# Espressylu-0_7.net
KiCad netlist of a schematic drawn in EAGLE
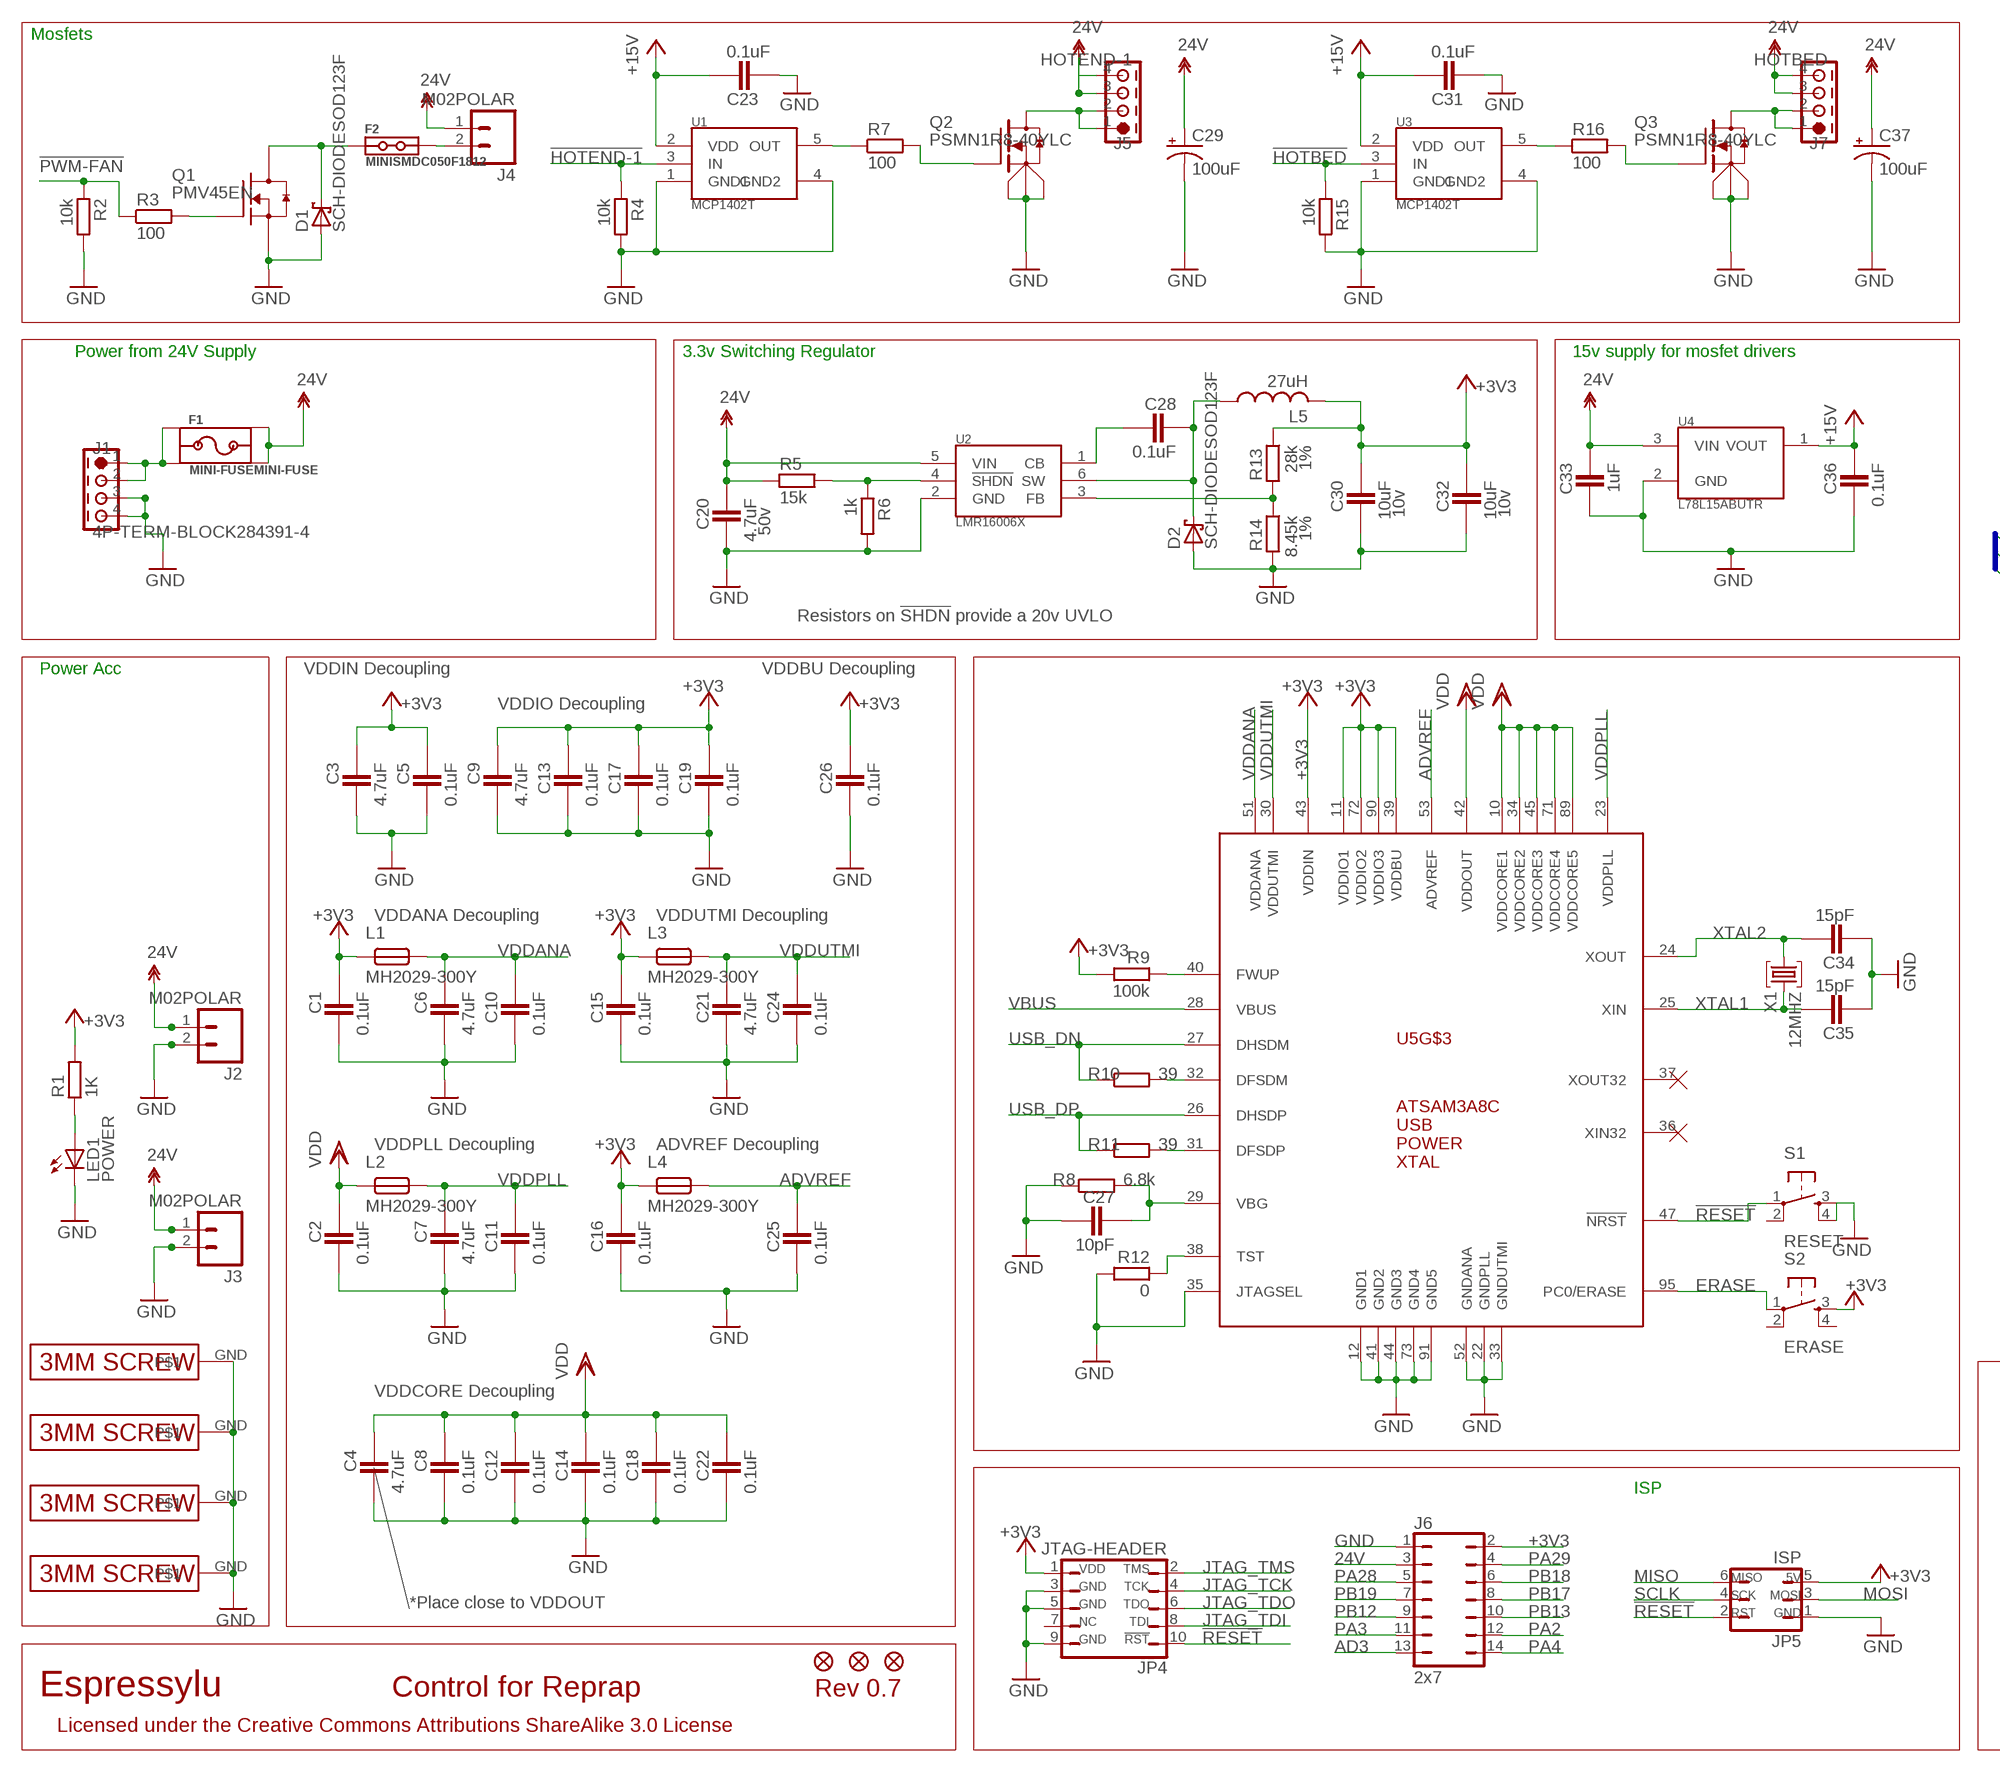
[diagram p0: schematic, sheet 1, part 1 of 2]
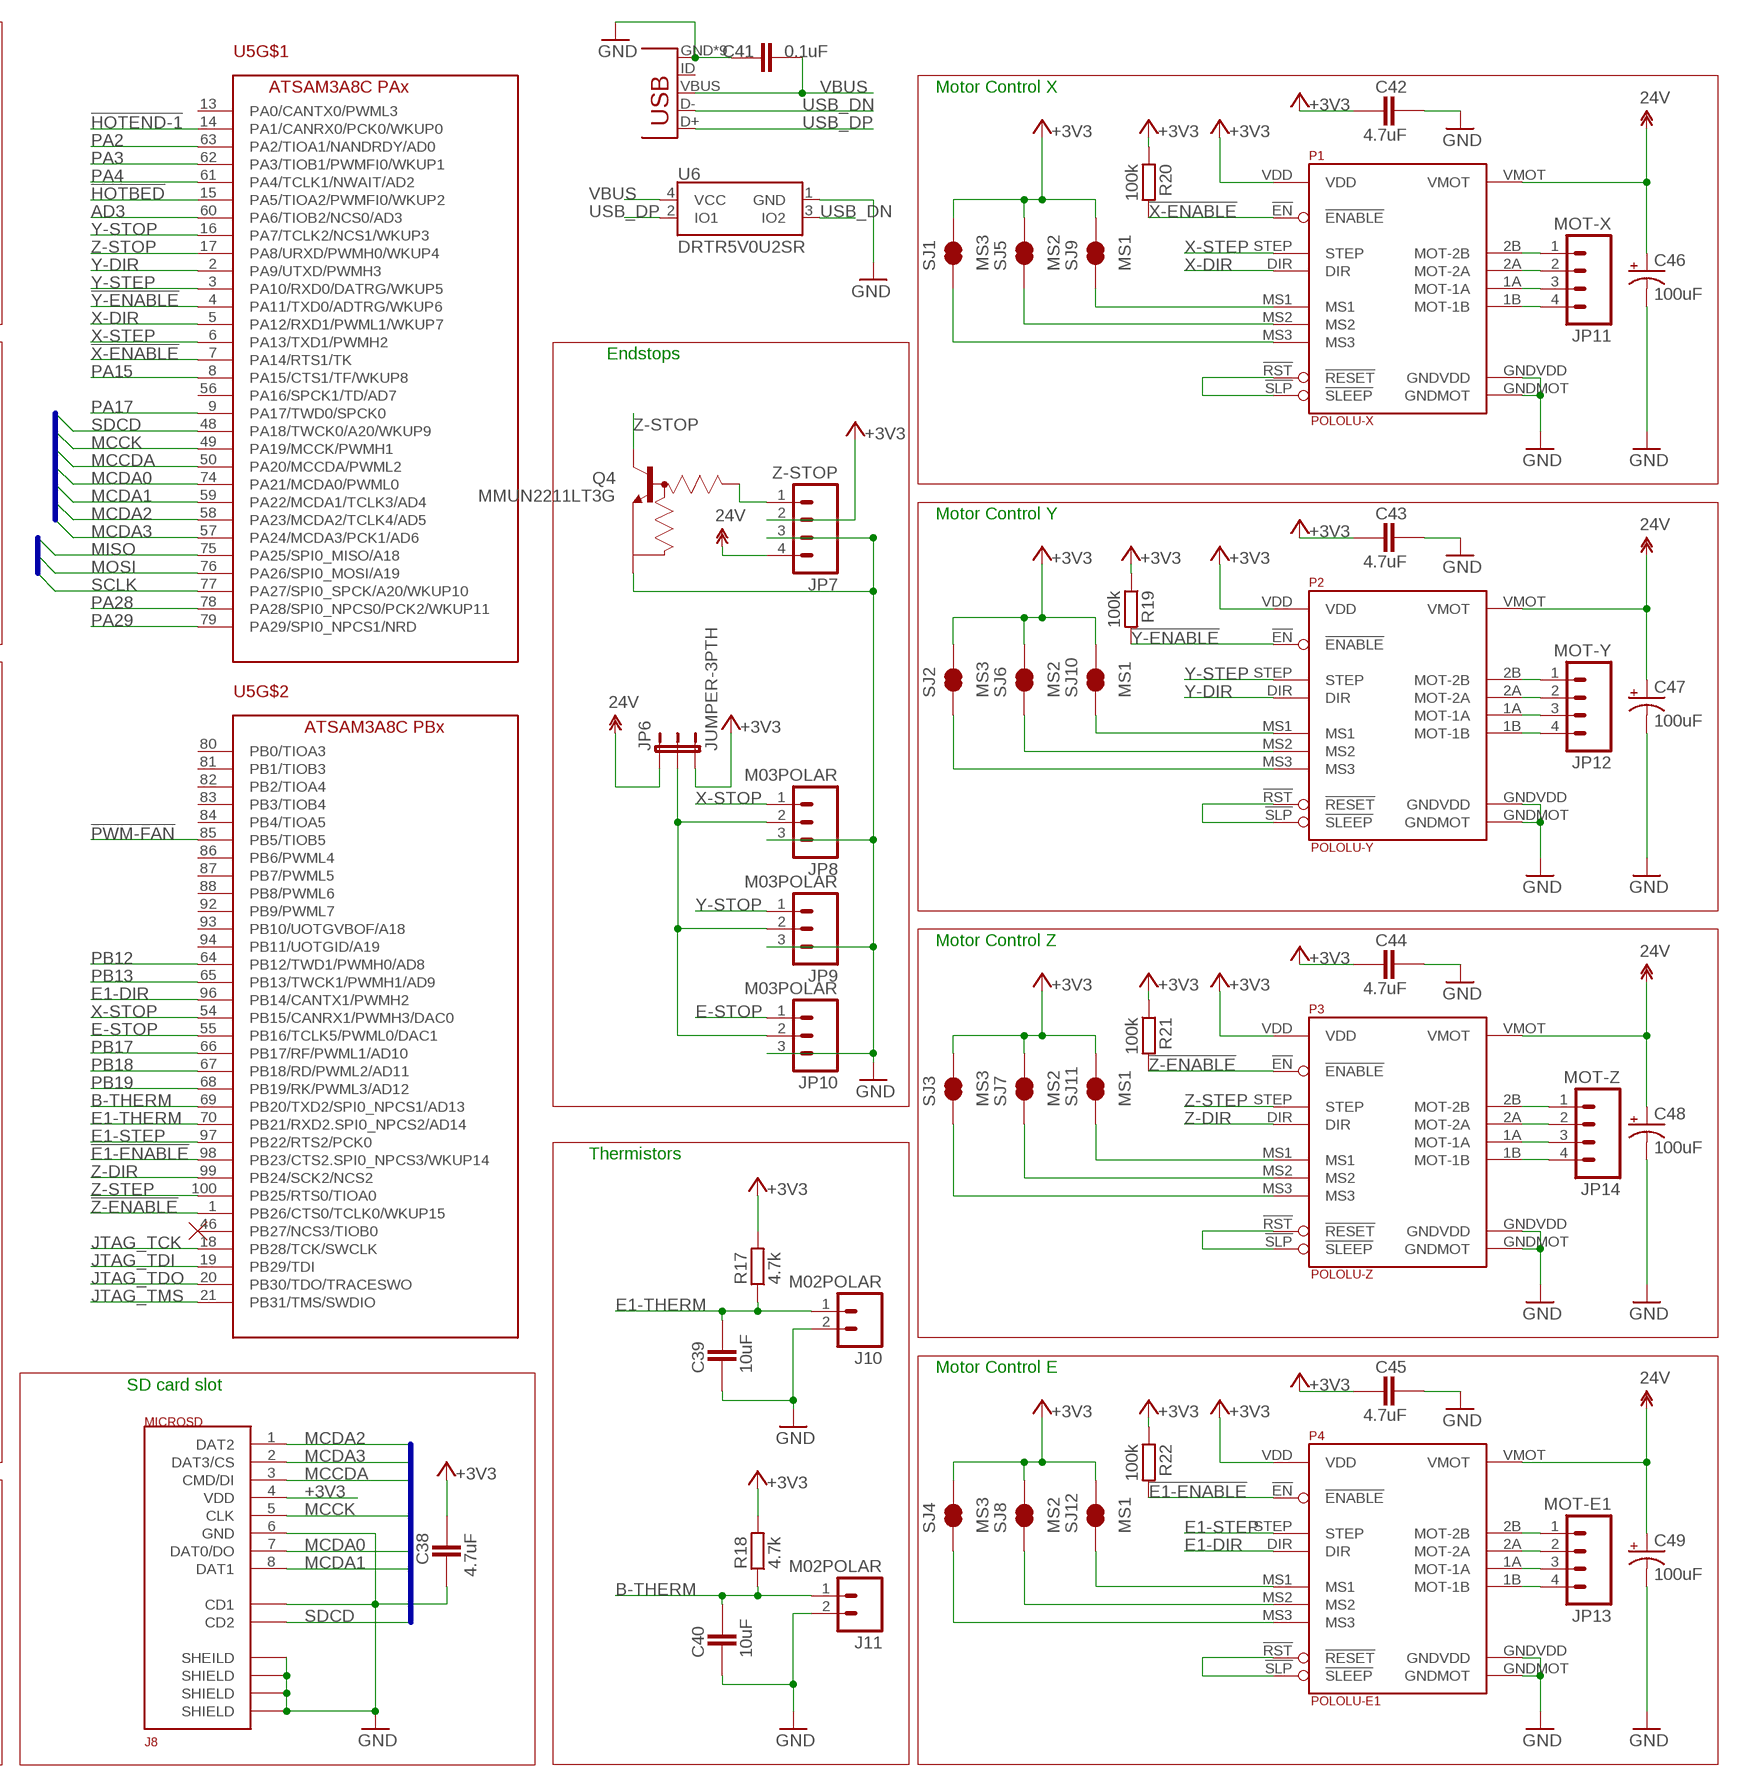
[diagram p1: schematic, sheet 1, part 2 of 2]

(export (version "E")
  (design (tool "Eeschema 10.0.6"))
  (components
    (comp (ref "C1")
      (value "0.1uF")
      (footprint "eagle-import:CAPC1005X60N")
      (fields
        (field (name "MANUFACTURER") "Samsung")
        (field (name "MANUFACTURER_PART_NUMBER") "CL05A104KQ5NNNC")
        (field (name "TOLERANCE") "10%")
      )
      (libsource (lib "eagle-import") (part "CAPACITOR_0402"))
    )
    (comp (ref "C2")
      (value "0.1uF")
      (footprint "eagle-import:CAPC1005X60N")
      (fields
        (field (name "MANUFACTURER") "Samsung")
        (field (name "MANUFACTURER_PART_NUMBER") "CL05A104KQ5NNNC")
        (field (name "TOLERANCE") "10%")
      )
      (libsource (lib "eagle-import") (part "CAPACITOR_0402"))
    )
    (comp (ref "C3")
      (value "4.7uF")
      (footprint "eagle-import:CAPC1608X92N")
      (fields
        (field (name "MANUFACTURER") "Samsung")
        (field (name "MANUFACTURER_PART_NUMBER") "CL10B475KQ8NQNC")
        (field (name "TOLERANCE") "10%")
        (field (name "VDC") "6.3V")
      )
      (libsource (lib "eagle-import") (part "CAPACITOR_0603"))
    )
    (comp (ref "C4")
      (value "4.7uF")
      (footprint "eagle-import:CAPC1608X92N")
      (fields
        (field (name "MANUFACTURER") "Samsung")
        (field (name "MANUFACTURER_PART_NUMBER") "CL10B475KQ8NQNC")
        (field (name "TOLERANCE") "10%")
        (field (name "VDC") "6.3V")
      )
      (libsource (lib "eagle-import") (part "CAPACITOR_0603"))
    )
    (comp (ref "C5")
      (value "0.1uF")
      (footprint "eagle-import:CAPC1005X60N")
      (fields
        (field (name "MANUFACTURER") "Samsung")
        (field (name "MANUFACTURER_PART_NUMBER") "CL05A104KQ5NNNC")
        (field (name "TOLERANCE") "10%")
      )
      (libsource (lib "eagle-import") (part "CAPACITOR_0402"))
    )
    (comp (ref "C6")
      (value "4.7uF")
      (footprint "eagle-import:CAPC1608X92N")
      (fields
        (field (name "MANUFACTURER") "Samsung")
        (field (name "MANUFACTURER_PART_NUMBER") "CL10B475KQ8NQNC")
        (field (name "TOLERANCE") "10%")
        (field (name "VDC") "6.3V")
      )
      (libsource (lib "eagle-import") (part "CAPACITOR_0603"))
    )
    (comp (ref "C7")
      (value "4.7uF")
      (footprint "eagle-import:CAPC1608X92N")
      (fields
        (field (name "MANUFACTURER") "Samsung")
        (field (name "MANUFACTURER_PART_NUMBER") "CL10B475KQ8NQNC")
        (field (name "TOLERANCE") "10%")
        (field (name "VDC") "6.3V")
      )
      (libsource (lib "eagle-import") (part "CAPACITOR_0603"))
    )
    (comp (ref "C8")
      (value "0.1uF")
      (footprint "eagle-import:CAPC1005X60N")
      (fields
        (field (name "MANUFACTURER") "Samsung")
        (field (name "MANUFACTURER_PART_NUMBER") "CL05A104KQ5NNNC")
        (field (name "TOLERANCE") "10%")
      )
      (libsource (lib "eagle-import") (part "CAPACITOR_0402"))
    )
    (comp (ref "C9")
      (value "4.7uF")
      (footprint "eagle-import:CAPC1608X92N")
      (fields
        (field (name "MANUFACTURER") "Samsung")
        (field (name "MANUFACTURER_PART_NUMBER") "CL10B475KQ8NQNC")
        (field (name "TOLERANCE") "10%")
        (field (name "VDC") "6.3V")
      )
      (libsource (lib "eagle-import") (part "CAPACITOR_0603"))
    )
    (comp (ref "C10")
      (value "0.1uF")
      (footprint "eagle-import:CAPC1005X60N")
      (fields
        (field (name "MANUFACTURER") "Samsung")
        (field (name "MANUFACTURER_PART_NUMBER") "CL05A104KQ5NNNC")
        (field (name "TOLERANCE") "10%")
      )
      (libsource (lib "eagle-import") (part "CAPACITOR_0402"))
    )
    (comp (ref "C11")
      (value "0.1uF")
      (footprint "eagle-import:CAPC1005X60N")
      (fields
        (field (name "MANUFACTURER") "Samsung")
        (field (name "MANUFACTURER_PART_NUMBER") "CL05A104KQ5NNNC")
        (field (name "TOLERANCE") "10%")
      )
      (libsource (lib "eagle-import") (part "CAPACITOR_0402"))
    )
    (comp (ref "C12")
      (value "0.1uF")
      (footprint "eagle-import:CAPC1005X60N")
      (fields
        (field (name "MANUFACTURER") "Samsung")
        (field (name "MANUFACTURER_PART_NUMBER") "CL05A104KQ5NNNC")
        (field (name "TOLERANCE") "10%")
      )
      (libsource (lib "eagle-import") (part "CAPACITOR_0402"))
    )
    (comp (ref "C13")
      (value "0.1uF")
      (footprint "eagle-import:CAPC1005X60N")
      (fields
        (field (name "MANUFACTURER") "Samsung")
        (field (name "MANUFACTURER_PART_NUMBER") "CL05A104KQ5NNNC")
        (field (name "TOLERANCE") "10%")
      )
      (libsource (lib "eagle-import") (part "CAPACITOR_0402"))
    )
    (comp (ref "C14")
      (value "0.1uF")
      (footprint "eagle-import:CAPC1005X60N")
      (fields
        (field (name "MANUFACTURER") "Samsung")
        (field (name "MANUFACTURER_PART_NUMBER") "CL05A104KQ5NNNC")
        (field (name "TOLERANCE") "10%")
      )
      (libsource (lib "eagle-import") (part "CAPACITOR_0402"))
    )
    (comp (ref "C15")
      (value "0.1uF")
      (footprint "eagle-import:CAPC1005X60N")
      (fields
        (field (name "MANUFACTURER") "Samsung")
        (field (name "MANUFACTURER_PART_NUMBER") "CL05A104KQ5NNNC")
        (field (name "TOLERANCE") "10%")
      )
      (libsource (lib "eagle-import") (part "CAPACITOR_0402"))
    )
    (comp (ref "C16")
      (value "0.1uF")
      (footprint "eagle-import:CAPC1005X60N")
      (fields
        (field (name "MANUFACTURER") "Samsung")
        (field (name "MANUFACTURER_PART_NUMBER") "CL05A104KQ5NNNC")
        (field (name "TOLERANCE") "10%")
      )
      (libsource (lib "eagle-import") (part "CAPACITOR_0402"))
    )
    (comp (ref "C17")
      (value "0.1uF")
      (footprint "eagle-import:CAPC1005X60N")
      (fields
        (field (name "MANUFACTURER") "Samsung")
        (field (name "MANUFACTURER_PART_NUMBER") "CL05A104KQ5NNNC")
        (field (name "TOLERANCE") "10%")
      )
      (libsource (lib "eagle-import") (part "CAPACITOR_0402"))
    )
    (comp (ref "C18")
      (value "0.1uF")
      (footprint "eagle-import:CAPC1005X60N")
      (fields
        (field (name "MANUFACTURER") "Samsung")
        (field (name "MANUFACTURER_PART_NUMBER") "CL05A104KQ5NNNC")
        (field (name "TOLERANCE") "10%")
      )
      (libsource (lib "eagle-import") (part "CAPACITOR_0402"))
    )
    (comp (ref "C19")
      (value "0.1uF")
      (footprint "eagle-import:CAPC1005X60N")
      (fields
        (field (name "MANUFACTURER") "Samsung")
        (field (name "MANUFACTURER_PART_NUMBER") "CL05A104KQ5NNNC")
        (field (name "TOLERANCE") "10%")
      )
      (libsource (lib "eagle-import") (part "CAPACITOR_0402"))
    )
    (comp (ref "C20")
      (value "4.7uF")
      (footprint "eagle-import:CAPC3215X168N")
      (fields
        (field (name "MANUFACTURER") "Yaiyo Yuden")
        (field (name "MANUFACTURER_PART_NUMBER") "UMK316AB7475KL-T")
        (field (name "TOLERANCE") "10%")
        (field (name "VDC") "50v")
      )
      (libsource (lib "eagle-import") (part "CAPACITOR_1206"))
    )
    (comp (ref "C21")
      (value "4.7uF")
      (footprint "eagle-import:CAPC1608X92N")
      (fields
        (field (name "MANUFACTURER") "Samsung")
        (field (name "MANUFACTURER_PART_NUMBER") "CL10B475KQ8NQNC")
        (field (name "TOLERANCE") "10%")
        (field (name "VDC") "6.3V")
      )
      (libsource (lib "eagle-import") (part "CAPACITOR_0603"))
    )
    (comp (ref "C22")
      (value "0.1uF")
      (footprint "eagle-import:CAPC1005X60N")
      (fields
        (field (name "MANUFACTURER") "Samsung")
        (field (name "MANUFACTURER_PART_NUMBER") "CL05A104KQ5NNNC")
        (field (name "TOLERANCE") "10%")
      )
      (libsource (lib "eagle-import") (part "CAPACITOR_0402"))
    )
    (comp (ref "C23")
      (value "0.1uF")
      (footprint "eagle-import:CAPC1005X60N")
      (fields (field (name "TOLERANCE") "20%"))
      (libsource (lib "eagle-import") (part "CAPACITOR_0402"))
    )
    (comp (ref "C24")
      (value "0.1uF")
      (footprint "eagle-import:CAPC1005X60N")
      (fields
        (field (name "MANUFACTURER") "Samsung")
        (field (name "MANUFACTURER_PART_NUMBER") "CL05A104KQ5NNNC")
        (field (name "TOLERANCE") "10%")
      )
      (libsource (lib "eagle-import") (part "CAPACITOR_0402"))
    )
    (comp (ref "C25")
      (value "0.1uF")
      (footprint "eagle-import:CAPC1005X60N")
      (fields
        (field (name "MANUFACTURER") "Samsung")
        (field (name "MANUFACTURER_PART_NUMBER") "CL05A104KQ5NNNC")
        (field (name "TOLERANCE") "10%")
      )
      (libsource (lib "eagle-import") (part "CAPACITOR_0402"))
    )
    (comp (ref "C26")
      (value "0.1uF")
      (footprint "eagle-import:CAPC1005X60N")
      (fields
        (field (name "MANUFACTURER") "Samsung")
        (field (name "MANUFACTURER_PART_NUMBER") "CL05A104KQ5NNNC")
        (field (name "TOLERANCE") "10%")
      )
      (libsource (lib "eagle-import") (part "CAPACITOR_0402"))
    )
    (comp (ref "C27")
      (value "10pF")
      (footprint "eagle-import:CAPC1005X60N")
      (fields
        (field (name "MANUFACTURER") "Samsung")
        (field (name "MANUFACTURER_PART_NUMBER") "CL10C100JB8NCNC")
        (field (name "TOLERANCE") "5%")
      )
      (libsource (lib "eagle-import") (part "CAPACITOR_0402"))
    )
    (comp (ref "C28")
      (value "0.1uF")
      (footprint "eagle-import:CAPC1005X60N")
      (fields
        (field (name "MANUFACTURER") "Samsung")
        (field (name "MANUFACTURER_PART_NUMBER") "CL10B104KB8NNNC")
        (field (name "TOLERANCE") "10%")
      )
      (libsource (lib "eagle-import") (part "CAPACITOR_0402"))
    )
    (comp (ref "C29")
      (value "100uF")
      (footprint "eagle-import:PANASONIC_D")
      (fields
        (field (name "MANUFACTURER") "Panasonic")
        (field (name "MANUFACTURER_PART_NUMBER") "EEE-FTH101XAP")
        (field (name "TOLERANCE") "20%")
      )
      (libsource (lib "eagle-import") (part "CPOL-USD"))
    )
    (comp (ref "C30")
      (value "10uF")
      (footprint "eagle-import:CAPC2012X145AN")
      (fields
        (field (name "MANUFACTURER") "Murata")
        (field (name "MANUFACTURER_PART_NUMBER") "GRM21BR71A106KE51L")
        (field (name "TOLERANCE") "10%")
        (field (name "VDC") "10v")
      )
      (libsource (lib "eagle-import") (part "CAPACITOR_0805"))
    )
    (comp (ref "C31")
      (value "0.1uF")
      (footprint "eagle-import:CAPC1005X60N")
      (fields (field (name "TOLERANCE") "20%"))
      (libsource (lib "eagle-import") (part "CAPACITOR_0402"))
    )
    (comp (ref "C32")
      (value "10uF")
      (footprint "eagle-import:CAPC2012X145AN")
      (fields
        (field (name "MANUFACTURER") "Murata")
        (field (name "MANUFACTURER_PART_NUMBER") "GRM21BR71A106KE51L")
        (field (name "TOLERANCE") "10%")
        (field (name "VDC") "10v")
      )
      (libsource (lib "eagle-import") (part "CAPACITOR_0805"))
    )
    (comp (ref "C33")
      (value "1uF")
      (footprint "eagle-import:CAPC1005X60N")
      (fields (field (name "TOLERANCE") "20%"))
      (libsource (lib "eagle-import") (part "CAPACITOR_0402"))
    )
    (comp (ref "C34")
      (value "15pF")
      (footprint "eagle-import:CAPC1005X60N")
      (fields
        (field (name "MANUFACTURER") "Samsung")
        (field (name "MANUFACTURER_PART_NUMBER") "CL05C150JB5NNNC")
        (field (name "TOLERANCE") "5%")
      )
      (libsource (lib "eagle-import") (part "CAPACITOR_0402"))
    )
    (comp (ref "C35")
      (value "15pF")
      (footprint "eagle-import:CAPC1005X60N")
      (fields
        (field (name "MANUFACTURER") "Samsung")
        (field (name "MANUFACTURER_PART_NUMBER") "CL05C150JB5NNNC")
        (field (name "TOLERANCE") "5%")
      )
      (libsource (lib "eagle-import") (part "CAPACITOR_0402"))
    )
    (comp (ref "C36")
      (value "0.1uF")
      (footprint "eagle-import:CAPC1005X60N")
      (fields (field (name "TOLERANCE") "20%"))
      (libsource (lib "eagle-import") (part "CAPACITOR_0402"))
    )
    (comp (ref "C37")
      (value "100uF")
      (footprint "eagle-import:PANASONIC_D")
      (fields
        (field (name "MANUFACTURER") "Panasonic")
        (field (name "MANUFACTURER_PART_NUMBER") "EEE-FTH101XAP")
        (field (name "TOLERANCE") "20%")
      )
      (libsource (lib "eagle-import") (part "CPOL-USD"))
    )
    (comp (ref "C38")
      (value "4.7uF")
      (footprint "eagle-import:CAPC1608X92N")
      (fields
        (field (name "MANUFACTURER") "Samsung")
        (field (name "MANUFACTURER_PART_NUMBER") "CL10B475KQ8NQNC")
        (field (name "TOLERANCE") "10%")
        (field (name "VDC") "6.3V")
      )
      (libsource (lib "eagle-import") (part "CAPACITOR_0603"))
    )
    (comp (ref "C39")
      (value "10uF")
      (footprint "eagle-import:CAPC1005X60N")
      (fields
        (field (name "MANUFACTURER") "Murata")
        (field (name "MANUFACTURER_PART_NUMBER") "GRM188R61C106MA73D")
        (field (name "TOLERANCE") "20%")
      )
      (libsource (lib "eagle-import") (part "CAPACITOR_0402"))
    )
    (comp (ref "C40")
      (value "10uF")
      (footprint "eagle-import:CAPC1005X60N")
      (fields
        (field (name "MANUFACTURER") "Murata")
        (field (name "MANUFACTURER_PART_NUMBER") "GRM188R61C106MA73D")
        (field (name "TOLERANCE") "20%")
      )
      (libsource (lib "eagle-import") (part "CAPACITOR_0402"))
    )
    (comp (ref "C41")
      (value "0.1uF")
      (footprint "eagle-import:CAPC1005X60N")
      (fields
        (field (name "MANUFACTURER") "Murata")
        (field (name "MANUFACTURER_PART_NUMBER") "GRM188R71C104KA01D")
        (field (name "TOLERANCE") "10%")
      )
      (libsource (lib "eagle-import") (part "CAPACITOR_0402"))
    )
    (comp (ref "C42")
      (value "4.7uF")
      (footprint "eagle-import:CAPC1608X92N")
      (fields
        (field (name "MANUFACTURER") "Samsung")
        (field (name "MANUFACTURER_PART_NUMBER") "CL10B475KQ8NQNC")
        (field (name "TOLERANCE") "10%")
        (field (name "VDC") "6.3V")
      )
      (libsource (lib "eagle-import") (part "CAPACITOR_0603"))
    )
    (comp (ref "C43")
      (value "4.7uF")
      (footprint "eagle-import:CAPC1608X92N")
      (fields
        (field (name "MANUFACTURER") "Samsung")
        (field (name "MANUFACTURER_PART_NUMBER") "CL10B475KQ8NQNC")
        (field (name "TOLERANCE") "10%")
        (field (name "VDC") "6.3V")
      )
      (libsource (lib "eagle-import") (part "CAPACITOR_0603"))
    )
    (comp (ref "C44")
      (value "4.7uF")
      (footprint "eagle-import:CAPC1608X92N")
      (fields
        (field (name "MANUFACTURER") "Samsung")
        (field (name "MANUFACTURER_PART_NUMBER") "CL10B475KQ8NQNC")
        (field (name "TOLERANCE") "10%")
        (field (name "VDC") "6.3V")
      )
      (libsource (lib "eagle-import") (part "CAPACITOR_0603"))
    )
    (comp (ref "C45")
      (value "4.7uF")
      (footprint "eagle-import:CAPC1608X92N")
      (fields
        (field (name "MANUFACTURER") "Samsung")
        (field (name "MANUFACTURER_PART_NUMBER") "CL10B475KQ8NQNC")
        (field (name "TOLERANCE") "10%")
        (field (name "VDC") "6.3V")
      )
      (libsource (lib "eagle-import") (part "CAPACITOR_0603"))
    )
    (comp (ref "C46")
      (value "100uF")
      (footprint "eagle-import:PANASONIC_D")
      (fields
        (field (name "MANUFACTURER") "Panasonic")
        (field (name "MANUFACTURER_PART_NUMBER") "EEE-FTH101XAP")
        (field (name "TOLERANCE") "20%")
      )
      (libsource (lib "eagle-import") (part "CPOL-USD"))
    )
    (comp (ref "C47")
      (value "100uF")
      (footprint "eagle-import:PANASONIC_D")
      (fields
        (field (name "MANUFACTURER") "Panasonic")
        (field (name "MANUFACTURER_PART_NUMBER") "EEE-FTH101XAP")
        (field (name "TOLERANCE") "20%")
      )
      (libsource (lib "eagle-import") (part "CPOL-USD"))
    )
    (comp (ref "C48")
      (value "100uF")
      (footprint "eagle-import:PANASONIC_D")
      (fields
        (field (name "MANUFACTURER") "Panasonic")
        (field (name "MANUFACTURER_PART_NUMBER") "EEE-FTH101XAP")
        (field (name "TOLERANCE") "20%")
      )
      (libsource (lib "eagle-import") (part "CPOL-USD"))
    )
    (comp (ref "C49")
      (value "100uF")
      (footprint "eagle-import:PANASONIC_D")
      (fields
        (field (name "MANUFACTURER") "Panasonic")
        (field (name "MANUFACTURER_PART_NUMBER") "EEE-FTH101XAP")
        (field (name "TOLERANCE") "20%")
      )
      (libsource (lib "eagle-import") (part "CPOL-USD"))
    )
    (comp (ref "D1")
      (value "SCH-DIODESOD123F")
      (footprint "eagle-import:SOD123F")
      (fields
        (field (name "MANUFACTURER") "NXP Semiconductors")
        (field (name "MANUFACTURER_PART_NUMBER") "PMEG4010CEH,115")
        (field (name "CURRENT") "1A")
        (field (name "MANUFACTURER_1") "NXP Semiconductors")
      )
      (libsource (lib "eagle-import") (part "SCH-DIODESOD123F"))
    )
    (comp (ref "D2")
      (value "SCH-DIODESOD123F")
      (footprint "eagle-import:SOD123F")
      (fields
        (field (name "MANUFACTURER") "NXP Semiconductors")
        (field (name "MANUFACTURER_PART_NUMBER") "PMEG4010CEH,115")
        (field (name "CURRENT") "1A")
        (field (name "MANUFACTURER_1") "NXP Semiconductors")
        (field (name "MANUFACTURER_PART_NUMBER_1") "PMEG4010CEH,115")
        (field (name "REVERSE_VOLTAGE") "40V")
      )
      (libsource (lib "eagle-import") (part "SCH-DIODESOD123F"))
    )
    (comp (ref "F1")
      (value "MINI-FUSEMINI-FUSE")
      (footprint "eagle-import:MINI_FUSE")
      (fields (field (name "MANUFACTURER") "Keystone") (field (name "MANUFACTURER_PART_NUMBER") "3568"))
      (libsource (lib "eagle-import") (part "MINI-FUSEMINI-FUSE"))
    )
    (comp (ref "F2")
      (value "MINISMDC050F1812")
      (footprint "eagle-import:MINISMDC")
      (fields
        (field (name "MANUFACTURER") "TE Connectivity")
        (field (name "MANUFACTURER_PART_NUMBER") "MINISMDC050F-2")
      )
      (libsource (lib "eagle-import") (part "MINISMDC050F1812"))
    )
    (comp (ref "J1")
      (value "4P-TERM-BLOCK284391-4")
      (footprint "eagle-import:284391-4")
      (fields
        (field (name "MANUFACTURER") "TE Connectivity")
        (field (name "MANUFACTURER_PART_NUMBER") "284391-4")
      )
      (libsource (lib "eagle-import") (part "4P-TERM-BLOCK284391-4"))
    )
    (comp (ref "J2")
      (value "M02POLAR")
      (footprint "eagle-import:MOLEX-1X2")
      (description "CONN HEADER 2POS .100 VERT TIN")
      (fields (field (name "MANUFACTURER") "Molex") (field (name "MANUFACTURER_PART_NUMBER") "0022272021"))
      (libsource (lib "eagle-import") (part "M02POLAR"))
    )
    (comp (ref "J3")
      (value "M02POLAR")
      (footprint "eagle-import:MOLEX-1X2")
      (description "CONN HEADER 2POS .100 VERT TIN")
      (fields (field (name "MANUFACTURER") "Molex") (field (name "MANUFACTURER_PART_NUMBER") "0022272021"))
      (libsource (lib "eagle-import") (part "M02POLAR"))
    )
    (comp (ref "J4")
      (value "M02POLAR")
      (footprint "eagle-import:MOLEX-1X2")
      (description "CONN HEADER 2POS .100 VERT TIN")
      (fields (field (name "MANUFACTURER") "Molex") (field (name "MANUFACTURER_PART_NUMBER") "0022272021"))
      (libsource (lib "eagle-import") (part "M02POLAR"))
    )
    (comp (ref "J5")
      (value "HOTEND-1")
      (footprint "eagle-import:284391-4")
      (fields
        (field (name "MANUFACTURER") "TE Connectivity")
        (field (name "MANUFACTURER_PART_NUMBER") "284391-4")
      )
      (libsource (lib "eagle-import") (part "4P-TERM-BLOCK284391-4"))
    )
    (comp (ref "J6")
      (value "2x7")
      (footprint "eagle-import:JP7Q")
      (description "DIL VERTICAL PC TAIL PIN HEADER")
      (fields (field (name "MANUFACTURER") "Harwin") (field (name "MANUFACTURER_PART_NUMBER") "M20-9980746"))
      (libsource (lib "eagle-import") (part "JP7Q"))
    )
    (comp (ref "J7")
      (value "HOTBED")
      (footprint "eagle-import:284391-4")
      (fields
        (field (name "MANUFACTURER") "TE Connectivity")
        (field (name "MANUFACTURER_PART_NUMBER") "284391-4")
      )
      (libsource (lib "eagle-import") (part "4P-TERM-BLOCK284391-4"))
    )
    (comp (ref "J8")
      (value "MICROSD")
      (footprint "eagle-import:AMPHENOL-MICROSD")
      (description "CONN MICRO SD CARD PUSH-PULL R/A")
      (fields
        (field (name "MANUFACTURER") "Amphenol")
        (field (name "MANUFACTURER_PART_NUMBER") "114-00841-68")
      )
      (libsource (lib "eagle-import") (part "MICROSD"))
    )
    (comp (ref "J9")
      (value "USB-MICRO-PTH")
      (footprint "eagle-import:USB-MICROB-PTH")
      (fields (field (name "MANUFACTURER") "FCI") (field (name "MANUFACTURER_PART_NUMBER") "10118194-0001LF"))
      (libsource (lib "eagle-import") (part "USB-MICRO-PTH"))
    )
    (comp (ref "J10")
      (value "M02POLAR")
      (footprint "eagle-import:MOLEX-1X2")
      (description "CONN HEADER 2POS .100 VERT TIN")
      (fields (field (name "MANUFACTURER") "Molex") (field (name "MANUFACTURER_PART_NUMBER") "0022272021"))
      (libsource (lib "eagle-import") (part "M02POLAR"))
    )
    (comp (ref "J11")
      (value "M02POLAR")
      (footprint "eagle-import:MOLEX-1X2")
      (description "CONN HEADER 2POS .100 VERT TIN")
      (fields (field (name "MANUFACTURER") "Molex") (field (name "MANUFACTURER_PART_NUMBER") "0022272021"))
      (libsource (lib "eagle-import") (part "M02POLAR"))
    )
    (comp (ref "JP1")
      (value "FIDUCIAL1X2.5")
      (footprint "eagle-import:FIDUCIAL-1X2.5")
      (libsource (lib "eagle-import") (part "FIDUCIAL1X2.5"))
    )
    (comp (ref "JP2")
      (value "FIDUCIAL1X2.5")
      (footprint "eagle-import:FIDUCIAL-1X2.5")
      (libsource (lib "eagle-import") (part "FIDUCIAL1X2.5"))
    )
    (comp (ref "JP3")
      (value "FIDUCIAL1X2.5")
      (footprint "eagle-import:FIDUCIAL-1X2.5")
      (libsource (lib "eagle-import") (part "FIDUCIAL1X2.5"))
    )
    (comp (ref "JP4")
      (value "JTAG-HEADER")
      (footprint "eagle-import:2X05-0.5-SMD")
      (fields
        (field (name "MANUFACTURER") "FCI")
        (field (name "MANUFACTURER_PART_NUMBER") "20021121-00010C4LF")
      )
      (libsource (lib "eagle-import") (part "JTAG-HEADER"))
    )
    (comp (ref "JP5")
      (value "ISP")
      (footprint "eagle-import:ISP")
      (libsource (lib "eagle-import") (part "PROGHEADER"))
    )
    (comp (ref "JP6")
      (value "JUMPER-3PTH")
      (footprint "eagle-import:1X03")
      (libsource (lib "eagle-import") (part "JUMPER-3PTH"))
    )
    (comp (ref "JP7")
      (value "Z-STOP")
      (footprint "eagle-import:MOLEX-1X4")
      (fields (field (name "MANUFACTURER") "Molex") (field (name "MANUFACTURER_PART_NUMBER") "0022272041"))
      (libsource (lib "eagle-import") (part "M04POLAR"))
    )
    (comp (ref "JP8")
      (value "M03POLAR")
      (footprint "eagle-import:MOLEX-1X3")
      (description "CONN HEADER 3POS .100 VERT TIN")
      (fields (field (name "MANUFACTURER") "Molex") (field (name "MANUFACTURER_PART_NUMBER") "0022272031"))
      (libsource (lib "eagle-import") (part "M03POLAR"))
    )
    (comp (ref "JP9")
      (value "M03POLAR")
      (footprint "eagle-import:MOLEX-1X3")
      (description "CONN HEADER 3POS .100 VERT TIN")
      (fields (field (name "MANUFACTURER") "Molex") (field (name "MANUFACTURER_PART_NUMBER") "0022272031"))
      (libsource (lib "eagle-import") (part "M03POLAR"))
    )
    (comp (ref "JP10")
      (value "M03POLAR")
      (footprint "eagle-import:MOLEX-1X3")
      (description "CONN HEADER 3POS .100 VERT TIN")
      (fields (field (name "MANUFACTURER") "Molex") (field (name "MANUFACTURER_PART_NUMBER") "0022272031"))
      (libsource (lib "eagle-import") (part "M03POLAR"))
    )
    (comp (ref "JP11")
      (value "MOT-X")
      (footprint "eagle-import:MOLEX-1X4")
      (fields (field (name "MANUFACTURER") "Molex") (field (name "MANUFACTURER_PART_NUMBER") "0022272041"))
      (libsource (lib "eagle-import") (part "M04POLAR"))
    )
    (comp (ref "JP12")
      (value "MOT-Y")
      (footprint "eagle-import:MOLEX-1X4")
      (fields (field (name "MANUFACTURER") "Molex") (field (name "MANUFACTURER_PART_NUMBER") "0022272041"))
      (libsource (lib "eagle-import") (part "M04POLAR"))
    )
    (comp (ref "JP13")
      (value "MOT-E1")
      (footprint "eagle-import:MOLEX-1X4")
      (fields (field (name "MANUFACTURER") "Molex") (field (name "MANUFACTURER_PART_NUMBER") "0022272041"))
      (libsource (lib "eagle-import") (part "M04POLAR"))
    )
    (comp (ref "JP14")
      (value "MOT-Z")
      (footprint "eagle-import:MOLEX-1X4")
      (fields (field (name "MANUFACTURER") "Molex") (field (name "MANUFACTURER_PART_NUMBER") "0022272041"))
      (libsource (lib "eagle-import") (part "M04POLAR"))
    )
    (comp (ref "L1")
      (value "MH2029-300Y")
      (footprint "eagle-import:FERRITE_BEAD_0805")
      (description "30 Ohm @ 100MHz")
      (fields (field (name "MANUFACTURER") "Bourns Inc"))
      (libsource (lib "eagle-import") (part "FERRITE_BEAD_0805"))
    )
    (comp (ref "L2")
      (value "MH2029-300Y")
      (footprint "eagle-import:FERRITE_BEAD_0805")
      (description "30 Ohm @ 100MHz")
      (fields (field (name "MANUFACTURER") "Bourns Inc"))
      (libsource (lib "eagle-import") (part "FERRITE_BEAD_0805"))
    )
    (comp (ref "L3")
      (value "MH2029-300Y")
      (footprint "eagle-import:FERRITE_BEAD_0805")
      (description "30 Ohm @ 100MHz")
      (fields (field (name "MANUFACTURER") "Bourns Inc"))
      (libsource (lib "eagle-import") (part "FERRITE_BEAD_0805"))
    )
    (comp (ref "L4")
      (value "MH2029-300Y")
      (footprint "eagle-import:FERRITE_BEAD_0805")
      (description "30 Ohm @ 100MHz")
      (fields (field (name "MANUFACTURER") "Bourns Inc"))
      (libsource (lib "eagle-import") (part "FERRITE_BEAD_0805"))
    )
    (comp (ref "L5")
      (value "27uH")
      (footprint "eagle-import:SDR0604")
      (fields
        (field (name "MANUFACTURER") "Bourns")
        (field (name "MANUFACTURER_1") "Bourns")
        (field (name "MANUFACTURER_PART_NUMBER") "SDR0604-270YL")
      )
      (libsource (lib "eagle-import") (part "INDUCTORSDR0604"))
    )
    (comp (ref "LED1")
      (value "POWER")
      (footprint "eagle-import:CHIPLED_0805")
      (fields
        (field (name "MANUFACTURER") "Kingbright")
        (field (name "MANUFACTURER_PART_NUMBER") "APT2012SGC")
      )
      (libsource (lib "eagle-import") (part "LEDCHIPLED_0805"))
    )
    (comp (ref "P1")
      (value "POLOLU-X")
      (footprint "eagle-import:POLOLU-STEPPER-PTH")
      (libsource (lib "eagle-import") (part "POLOLU-ALLEGRO"))
    )
    (comp (ref "P2")
      (value "POLOLU-Y")
      (footprint "eagle-import:POLOLU-STEPPER-PTH")
      (libsource (lib "eagle-import") (part "POLOLU-ALLEGRO"))
    )
    (comp (ref "P3")
      (value "POLOLU-Z")
      (footprint "eagle-import:POLOLU-STEPPER-PTH")
      (libsource (lib "eagle-import") (part "POLOLU-ALLEGRO"))
    )
    (comp (ref "P4")
      (value "POLOLU-E1")
      (footprint "eagle-import:POLOLU-STEPPER-PTH")
      (libsource (lib "eagle-import") (part "POLOLU-ALLEGRO"))
    )
    (comp (ref "Q1")
      (value "PMV45EN")
      (footprint "eagle-import:SOT23C")
      (fields
        (field (name "MANUFACTURER") "International Rectifier")
        (field (name "MANUFACTURER_PART_NUMBER") "IRLML2060TRPBF")
        (field (name "VOLTAGE") "60V")
      )
      (libsource (lib "eagle-import") (part "MOSFET-NCH_SOT-23"))
    )
    (comp (ref "Q2")
      (value "PSMN1R8-40YLC")
      (footprint "eagle-import:LFPACK-POWERPAK-SO8")
      (fields
        (field (name "MANUFACTURER") "NXP Semiconductors")
        (field (name "MANUFACTURER_PART_NUMBER") "PSMN1R8-40YLC,115")
        (field (name "VOLTAGE") "40V")
      )
      (libsource (lib "eagle-import") (part "PSMN1R8-40YLCPOWERPACK-S08"))
    )
    (comp (ref "Q3")
      (value "PSMN1R8-40YLC")
      (footprint "eagle-import:LFPACK-POWERPAK-SO8")
      (fields
        (field (name "MANUFACTURER") "NXP Semiconductors")
        (field (name "MANUFACTURER_PART_NUMBER") "PSMN1R8-40YLC,115")
        (field (name "VOLTAGE") "40V")
      )
      (libsource (lib "eagle-import") (part "PSMN1R8-40YLCPOWERPACK-S08"))
    )
    (comp (ref "Q4")
      (value "MMUN2211LT3G")
      (footprint "eagle-import:SOT23C")
      (description "TRANS PREBIAS NPN 246MW SOT23-3")
      (fields (field (name "MANUFACTURER") "ON Semiconductor"))
      (libsource (lib "eagle-import") (part "TRANSISTOR_NPN_BIASSOT23C"))
    )
    (comp (ref "R1")
      (value "1K")
      (footprint "eagle-import:RESC1608X55N")
      (libsource (lib "eagle-import") (part "RESISTOR_0603"))
    )
    (comp (ref "R2")
      (value "10k")
      (footprint "eagle-import:RESC1005X40AN")
      (libsource (lib "eagle-import") (part "RESISTOR_0402"))
    )
    (comp (ref "R3")
      (value "100")
      (footprint "eagle-import:RESC1005X40AN")
      (libsource (lib "eagle-import") (part "RESISTOR_0402"))
    )
    (comp (ref "R4")
      (value "10k")
      (footprint "eagle-import:RESC1005X40AN")
      (libsource (lib "eagle-import") (part "RESISTOR_0402"))
    )
    (comp (ref "R5")
      (value "15k")
      (footprint "eagle-import:RESC1005X40AN")
      (libsource (lib "eagle-import") (part "RESISTOR_0402"))
    )
    (comp (ref "R6")
      (value "1k")
      (footprint "eagle-import:RESC1005X40AN")
      (libsource (lib "eagle-import") (part "RESISTOR_0402"))
    )
    (comp (ref "R7")
      (value "100")
      (footprint "eagle-import:RESC1005X40AN")
      (libsource (lib "eagle-import") (part "RESISTOR_0402"))
    )
    (comp (ref "R8")
      (value "6.8k")
      (footprint "eagle-import:RESC1005X40AN")
      (fields (field (name "TOLERANCE") "1%"))
      (libsource (lib "eagle-import") (part "RESISTOR_0402"))
    )
    (comp (ref "R9")
      (value "100k")
      (footprint "eagle-import:RESC1005X40AN")
      (libsource (lib "eagle-import") (part "RESISTOR_0402"))
    )
    (comp (ref "R10")
      (value "39")
      (footprint "eagle-import:RESC1005X40AN")
      (fields (field (name "TOLERANCE") "1%"))
      (libsource (lib "eagle-import") (part "RESISTOR_0402"))
    )
    (comp (ref "R11")
      (value "39")
      (footprint "eagle-import:RESC1005X40AN")
      (fields (field (name "TOLERANCE") "1%"))
      (libsource (lib "eagle-import") (part "RESISTOR_0402"))
    )
    (comp (ref "R12")
      (value "0")
      (footprint "eagle-import:RESC1005X40AN")
      (libsource (lib "eagle-import") (part "RESISTOR_0402"))
    )
    (comp (ref "R13")
      (value "28k")
      (footprint "eagle-import:RESC1005X40AN")
      (fields (field (name "TOLERANCE") "1%"))
      (libsource (lib "eagle-import") (part "RESISTOR_0402"))
    )
    (comp (ref "R14")
      (value "8.45k")
      (footprint "eagle-import:RESC1005X40AN")
      (fields (field (name "TOLERANCE") "1%"))
      (libsource (lib "eagle-import") (part "RESISTOR_0402"))
    )
    (comp (ref "R15")
      (value "10k")
      (footprint "eagle-import:RESC1005X40AN")
      (libsource (lib "eagle-import") (part "RESISTOR_0402"))
    )
    (comp (ref "R16")
      (value "100")
      (footprint "eagle-import:RESC1005X40AN")
      (libsource (lib "eagle-import") (part "RESISTOR_0402"))
    )
    (comp (ref "R17")
      (value "4.7k")
      (footprint "eagle-import:RESC1005X40AN")
      (libsource (lib "eagle-import") (part "RESISTOR_0402"))
    )
    (comp (ref "R18")
      (value "4.7k")
      (footprint "eagle-import:RESC1005X40AN")
      (libsource (lib "eagle-import") (part "RESISTOR_0402"))
    )
    (comp (ref "R19")
      (value "100k")
      (footprint "eagle-import:RESC1005X40AN")
      (libsource (lib "eagle-import") (part "RESISTOR_0402"))
    )
    (comp (ref "R20")
      (value "100k")
      (footprint "eagle-import:RESC1005X40AN")
      (libsource (lib "eagle-import") (part "RESISTOR_0402"))
    )
    (comp (ref "R21")
      (value "100k")
      (footprint "eagle-import:RESC1005X40AN")
      (libsource (lib "eagle-import") (part "RESISTOR_0402"))
    )
    (comp (ref "R22")
      (value "100k")
      (footprint "eagle-import:RESC1005X40AN")
      (libsource (lib "eagle-import") (part "RESISTOR_0402"))
    )
    (comp (ref "S1")
      (value "RESET")
      (footprint "eagle-import:SWITCH-SMD-4P")
      (fields
        (field (name "MANUFACTURER") "TE Connectivity")
        (field (name "MANUFACTURER_PART_NUMBER") "FSM6JSMA")
      )
      (libsource (lib "eagle-import") (part "TAC_SWITCH_4P4P-SMD"))
    )
    (comp (ref "S2")
      (value "ERASE")
      (footprint "eagle-import:SWITCH-SMD-4P")
      (fields
        (field (name "MANUFACTURER") "TE Connectivity")
        (field (name "MANUFACTURER_PART_NUMBER") "FSM6JSMA")
      )
      (libsource (lib "eagle-import") (part "TAC_SWITCH_4P4P-SMD"))
    )
    (comp (ref "SCREW1")
      (value "3MM-SCREW")
      (footprint "eagle-import:PLATEDSCREW")
      (libsource (lib "eagle-import") (part "3MM-SCREW"))
    )
    (comp (ref "SCREW2")
      (value "3MM-SCREW")
      (footprint "eagle-import:PLATEDSCREW")
      (libsource (lib "eagle-import") (part "3MM-SCREW"))
    )
    (comp (ref "SCREW3")
      (value "3MM-SCREW")
      (footprint "eagle-import:PLATEDSCREW")
      (libsource (lib "eagle-import") (part "3MM-SCREW"))
    )
    (comp (ref "SCREW4")
      (value "3MM-SCREW")
      (footprint "eagle-import:PLATEDSCREW")
      (libsource (lib "eagle-import") (part "3MM-SCREW"))
    )
    (comp (ref "SJ1")
      (value "MS3")
      (footprint "eagle-import:SJ_2S-TRACE")
      (libsource (lib "eagle-import") (part "SOLDERJUMPER-NCSJ-TRACE"))
    )
    (comp (ref "SJ2")
      (value "MS3")
      (footprint "eagle-import:SJ_2S-TRACE")
      (libsource (lib "eagle-import") (part "SOLDERJUMPER-NCSJ-TRACE"))
    )
    (comp (ref "SJ3")
      (value "MS3")
      (footprint "eagle-import:SJ_2S-TRACE")
      (libsource (lib "eagle-import") (part "SOLDERJUMPER-NCSJ-TRACE"))
    )
    (comp (ref "SJ4")
      (value "MS3")
      (footprint "eagle-import:SJ_2S-TRACE")
      (libsource (lib "eagle-import") (part "SOLDERJUMPER-NCSJ-TRACE"))
    )
    (comp (ref "SJ5")
      (value "MS2")
      (footprint "eagle-import:SJ_2S-TRACE")
      (libsource (lib "eagle-import") (part "SOLDERJUMPER-NCSJ-TRACE"))
    )
    (comp (ref "SJ6")
      (value "MS2")
      (footprint "eagle-import:SJ_2S-TRACE")
      (libsource (lib "eagle-import") (part "SOLDERJUMPER-NCSJ-TRACE"))
    )
    (comp (ref "SJ7")
      (value "MS2")
      (footprint "eagle-import:SJ_2S-TRACE")
      (libsource (lib "eagle-import") (part "SOLDERJUMPER-NCSJ-TRACE"))
    )
    (comp (ref "SJ8")
      (value "MS2")
      (footprint "eagle-import:SJ_2S-TRACE")
      (libsource (lib "eagle-import") (part "SOLDERJUMPER-NCSJ-TRACE"))
    )
    (comp (ref "SJ9")
      (value "MS1")
      (footprint "eagle-import:SJ_2S-TRACE")
      (libsource (lib "eagle-import") (part "SOLDERJUMPER-NCSJ-TRACE"))
    )
    (comp (ref "SJ10")
      (value "MS1")
      (footprint "eagle-import:SJ_2S-TRACE")
      (libsource (lib "eagle-import") (part "SOLDERJUMPER-NCSJ-TRACE"))
    )
    (comp (ref "SJ11")
      (value "MS1")
      (footprint "eagle-import:SJ_2S-TRACE")
      (libsource (lib "eagle-import") (part "SOLDERJUMPER-NCSJ-TRACE"))
    )
    (comp (ref "SJ12")
      (value "MS1")
      (footprint "eagle-import:SJ_2S-TRACE")
      (libsource (lib "eagle-import") (part "SOLDERJUMPER-NCSJ-TRACE"))
    )
    (comp (ref "U1")
      (value "MCP1402T")
      (footprint "eagle-import:SOT23-5")
      (fields
        (field (name "MANUFACTURER") "Microchip")
        (field (name "MANUFACTURER_PART_NUMBER") "MCP1402T-E/OT")
      )
      (libsource (lib "eagle-import") (part "MCP1402T"))
    )
    (comp (ref "U2")
      (value "LMR16006X")
      (footprint "eagle-import:TSOT6")
      (fields
        (field (name "MANUFACTURER") "Texas Instruments")
        (field (name "MANUFACTURER_PART_NUMBER") "LMR16006XDDCT")
      )
      (libsource (lib "eagle-import") (part "LMR16006X"))
    )
    (comp (ref "U3")
      (value "MCP1402T")
      (footprint "eagle-import:SOT23-5")
      (fields
        (field (name "MANUFACTURER") "Microchip")
        (field (name "MANUFACTURER_PART_NUMBER") "MCP1402T-E/OT")
      )
      (libsource (lib "eagle-import") (part "MCP1402T"))
    )
    (comp (ref "U4")
      (value "L78L15ABUTR")
      (footprint "eagle-import:SOT89")
      (fields (field (name "MANUFACTURER") "STMicroelectronics"))
      (libsource (lib "eagle-import") (part "L78L15ABUTR"))
    )
    (comp (ref "U5")
      (value "ATSAM3A8C-LQFP100")
      (footprint "eagle-import:LQFP100")
      (fields (field (name "MANUFACTURER") "Atmel") (field (name "MANUFACTURER_PART_NUMBER") "ATSAM3A8C"))
      (libsource (lib "eagle-import") (part "ATSAM3A8C-LQFP100"))
    )
    (comp (ref "U6")
      (value "DRTR5V0U2SR")
      (footprint "eagle-import:SOT143-R")
      (fields
        (field (name "MANUFACTURER") "Diodes Incorporated")
        (field (name "MANUFACTURER_PART_NUMBER") "DTR5V0U2SR")
      )
      (libsource (lib "eagle-import") (part "DRTR5V0U2SR"))
    )
    (comp (ref "X1")
      (value "12MHZ")
      (footprint "eagle-import:NDK-XTAL")
      (fields
        (field (name "MANUFACTURER") "Abracon LLC")
        (field (name "MANUFACTURER_PART_NUMBER") "ABM3-12.000MHZ-B2-T")
      )
      (libsource (lib "eagle-import") (part "XTAL"))
    )
  )
  (nets
    (net (code "1") (name "+3V3") (class "Default")
      (node (ref "C1") (pin "1") (pinfunction "1_1") (pintype "passive"))
      (node (ref "C13") (pin "1") (pinfunction "1_1") (pintype "passive"))
      (node (ref "C15") (pin "1") (pinfunction "1_1") (pintype "passive"))
      (node (ref "C16") (pin "1") (pinfunction "1_1") (pintype "passive"))
      (node (ref "C17") (pin "1") (pinfunction "1_1") (pintype "passive"))
      (node (ref "C19") (pin "1") (pinfunction "1_1") (pintype "passive"))
      (node (ref "C26") (pin "1") (pinfunction "1_1") (pintype "passive"))
      (node (ref "C3") (pin "1") (pinfunction "1_1") (pintype "passive"))
      (node (ref "C30") (pin "1") (pinfunction "1_1") (pintype "passive"))
      (node (ref "C32") (pin "1") (pinfunction "1_1") (pintype "passive"))
      (node (ref "C38") (pin "1") (pinfunction "1_1") (pintype "passive"))
      (node (ref "C42") (pin "2") (pinfunction "2_2") (pintype "passive"))
      (node (ref "C43") (pin "2") (pinfunction "2_2") (pintype "passive"))
      (node (ref "C44") (pin "2") (pinfunction "2_2") (pintype "passive"))
      (node (ref "C45") (pin "2") (pinfunction "2_2") (pintype "passive"))
      (node (ref "C5") (pin "1") (pinfunction "1_1") (pintype "passive"))
      (node (ref "C9") (pin "1") (pinfunction "1_1") (pintype "passive"))
      (node (ref "J6") (pin "2") (pinfunction "2_2") (pintype "passive"))
      (node (ref "J8") (pin "4") (pinfunction "VDD_4") (pintype "power_in"))
      (node (ref "JP4") (pin "1") (pinfunction "1_1") (pintype "passive"))
      (node (ref "JP5") (pin "5") (pinfunction "5_5") (pintype "passive"))
      (node (ref "JP6") (pin "3") (pinfunction "3_3") (pintype "passive"))
      (node (ref "JP7") (pin "2") (pinfunction "2_2") (pintype "passive"))
      (node (ref "L1") (pin "1") (pinfunction "1_1") (pintype "passive"))
      (node (ref "L3") (pin "1") (pinfunction "1_1") (pintype "passive"))
      (node (ref "L4") (pin "1") (pinfunction "1_1") (pintype "passive"))
      (node (ref "L5") (pin "2") (pinfunction "2_2") (pintype "passive"))
      (node (ref "P1") (pin "VDD") (pinfunction "VDD_VDD") (pintype "power_in"))
      (node (ref "P2") (pin "VDD") (pinfunction "VDD_VDD") (pintype "power_in"))
      (node (ref "P3") (pin "VDD") (pinfunction "VDD_VDD") (pintype "power_in"))
      (node (ref "P4") (pin "VDD") (pinfunction "VDD_VDD") (pintype "power_in"))
      (node (ref "R1") (pin "2") (pinfunction "2_2") (pintype "passive"))
      (node (ref "R13") (pin "1") (pinfunction "1_1") (pintype "passive"))
      (node (ref "R17") (pin "2") (pinfunction "2_2") (pintype "passive"))
      (node (ref "R18") (pin "2") (pinfunction "2_2") (pintype "passive"))
      (node (ref "R19") (pin "1") (pinfunction "1_1") (pintype "passive"))
      (node (ref "R20") (pin "1") (pinfunction "1_1") (pintype "passive"))
      (node (ref "R21") (pin "1") (pinfunction "1_1") (pintype "passive"))
      (node (ref "R22") (pin "1") (pinfunction "1_1") (pintype "passive"))
      (node (ref "R9") (pin "2") (pinfunction "2_2") (pintype "passive"))
      (node (ref "S2") (pin "3") (pinfunction "3_3") (pintype "passive"))
      (node (ref "SJ1") (pin "2") (pinfunction "2_2") (pintype "passive"))
      (node (ref "SJ10") (pin "2") (pinfunction "2_2") (pintype "passive"))
      (node (ref "SJ11") (pin "2") (pinfunction "2_2") (pintype "passive"))
      (node (ref "SJ12") (pin "2") (pinfunction "2_2") (pintype "passive"))
      (node (ref "SJ2") (pin "2") (pinfunction "2_2") (pintype "passive"))
      (node (ref "SJ3") (pin "2") (pinfunction "2_2") (pintype "passive"))
      (node (ref "SJ4") (pin "2") (pinfunction "2_2") (pintype "passive"))
      (node (ref "SJ5") (pin "2") (pinfunction "2_2") (pintype "passive"))
      (node (ref "SJ6") (pin "2") (pinfunction "2_2") (pintype "passive"))
      (node (ref "SJ7") (pin "2") (pinfunction "2_2") (pintype "passive"))
      (node (ref "SJ8") (pin "2") (pinfunction "2_2") (pintype "passive"))
      (node (ref "SJ9") (pin "2") (pinfunction "2_2") (pintype "passive"))
      (node (ref "U5") (pin "11") (pinfunction "VDDIO1_11") (pintype "power_in"))
      (node (ref "U5") (pin "39") (pinfunction "VDDBU_39") (pintype "power_in"))
      (node (ref "U5") (pin "43") (pinfunction "VDDIN_43") (pintype "power_in"))
      (node (ref "U5") (pin "72") (pinfunction "VDDIO2_72") (pintype "power_in"))
      (node (ref "U5") (pin "90") (pinfunction "VDDIO3_90") (pintype "power_in"))
    )
    (net (code "2") (name "+15V") (class "Default")
      (node (ref "C23") (pin "1") (pinfunction "1_1") (pintype "passive"))
      (node (ref "C31") (pin "1") (pinfunction "1_1") (pintype "passive"))
      (node (ref "C36") (pin "1") (pinfunction "1_1") (pintype "passive"))
      (node (ref "U1") (pin "2") (pinfunction "VDD_2") (pintype "power_in"))
      (node (ref "U3") (pin "2") (pinfunction "VDD_2") (pintype "power_in"))
      (node (ref "U4") (pin "1") (pinfunction "VOUT_1") (pintype "passive"))
    )
    (net (code "3") (name "/AD3") (class "Default")
      (node (ref "J6") (pin "13") (pinfunction "13_13") (pintype "passive"))
      (node (ref "U5") (pin "60") (pinfunction "PA6/TIOB2/NCS0/AD3_60") (pintype "bidirectional"))
    )
    (net (code "4") (name "/ADVREF") (class "Default")
      (node (ref "C25") (pin "1") (pinfunction "1_1") (pintype "passive"))
      (node (ref "L4") (pin "2") (pinfunction "2_2") (pintype "passive"))
      (node (ref "U5") (pin "53") (pinfunction "ADVREF_53") (pintype "power_in"))
    )
    (net (code "5") (name "/B-THERM") (class "Default")
      (node (ref "C40") (pin "2") (pinfunction "2_2") (pintype "passive"))
      (node (ref "J11") (pin "1") (pinfunction "1_1") (pintype "passive"))
      (node (ref "R18") (pin "1") (pinfunction "1_1") (pintype "passive"))
      (node (ref "U5") (pin "69") (pinfunction "PB20/TXD2/SPI0_NPCS1/AD13_69") (pintype "bidirectional"))
    )
    (net (code "6") (name "/E-STOP") (class "Default")
      (node (ref "JP10") (pin "1") (pinfunction "1_1") (pintype "passive"))
      (node (ref "U5") (pin "55") (pinfunction "PB16/TCLK5/PWML0/DAC1_55") (pintype "bidirectional"))
    )
    (net (code "7") (name "/E1-DIR") (class "Default")
      (node (ref "P4") (pin "DIR") (pinfunction "DIR_DIR") (pintype "bidirectional"))
      (node (ref "U5") (pin "96") (pinfunction "PB14/CANTX1/PWMH2_96") (pintype "bidirectional"))
    )
    (net (code "8") (name "/E1-STEP") (class "Default")
      (node (ref "P4") (pin "STEP") (pinfunction "STEP_STEP") (pintype "bidirectional"))
      (node (ref "U5") (pin "97") (pinfunction "PB22/RTS2/PCK0_97") (pintype "bidirectional"))
    )
    (net (code "9") (name "/E1-THERM") (class "Default")
      (node (ref "C39") (pin "2") (pinfunction "2_2") (pintype "passive"))
      (node (ref "J10") (pin "1") (pinfunction "1_1") (pintype "passive"))
      (node (ref "R17") (pin "1") (pinfunction "1_1") (pintype "passive"))
      (node (ref "U5") (pin "70") (pinfunction "PB21/RXD2.SPI0_NPCS2/AD14_70") (pintype "bidirectional"))
    )
    (net (code "10") (name "/ERASE") (class "Default")
      (node (ref "S2") (pin "1") (pinfunction "1_1") (pintype "passive"))
      (node (ref "U5") (pin "95") (pinfunction "PC0/ERASE_95") (pintype "bidirectional"))
    )
    (net (code "11") (name "/JTAG_TCK") (class "Default")
      (node (ref "JP4") (pin "4") (pinfunction "4_4") (pintype "passive"))
      (node (ref "U5") (pin "18") (pinfunction "PB28/TCK/SWCLK_18") (pintype "bidirectional"))
    )
    (net (code "12") (name "/JTAG_TDI") (class "Default")
      (node (ref "JP4") (pin "8") (pinfunction "8_8") (pintype "passive"))
      (node (ref "U5") (pin "19") (pinfunction "PB29/TDI_19") (pintype "bidirectional"))
    )
    (net (code "13") (name "/JTAG_TDO") (class "Default")
      (node (ref "JP4") (pin "6") (pinfunction "6_6") (pintype "passive"))
      (node (ref "U5") (pin "20") (pinfunction "PB30/TDO/TRACESWO_20") (pintype "bidirectional"))
    )
    (net (code "14") (name "/JTAG_TMS") (class "Default")
      (node (ref "JP4") (pin "2") (pinfunction "2_2") (pintype "passive"))
      (node (ref "U5") (pin "21") (pinfunction "PB31/TMS/SWDIO_21") (pintype "bidirectional"))
    )
    (net (code "15") (name "/MCCDA") (class "Default")
      (node (ref "J8") (pin "3") (pinfunction "CMD/DI_3") (pintype "input"))
      (node (ref "U5") (pin "50") (pinfunction "PA20/MCCDA/PWML2_50") (pintype "bidirectional"))
    )
    (net (code "16") (name "/MCCK") (class "Default")
      (node (ref "J8") (pin "5") (pinfunction "CLK_5") (pintype "input"))
      (node (ref "U5") (pin "49") (pinfunction "PA19/MCCK/PWMH1_49") (pintype "bidirectional"))
    )
    (net (code "17") (name "/MCDA0") (class "Default")
      (node (ref "J8") (pin "7") (pinfunction "DAT0/DO_7") (pintype "bidirectional"))
      (node (ref "U5") (pin "74") (pinfunction "PA21/MCDA0/PWML0_74") (pintype "bidirectional"))
    )
    (net (code "18") (name "/MCDA1") (class "Default")
      (node (ref "J8") (pin "8") (pinfunction "DAT1_8") (pintype "bidirectional"))
      (node (ref "U5") (pin "59") (pinfunction "PA22/MCDA1/TCLK3/AD4_59") (pintype "bidirectional"))
    )
    (net (code "19") (name "/MCDA2") (class "Default")
      (node (ref "J8") (pin "1") (pinfunction "DAT2_1") (pintype "bidirectional"))
      (node (ref "U5") (pin "58") (pinfunction "PA23/MCDA2/TCLK4/AD5_58") (pintype "bidirectional"))
    )
    (net (code "20") (name "/MCDA3") (class "Default")
      (node (ref "J8") (pin "2") (pinfunction "DAT3/CS_2") (pintype "bidirectional"))
      (node (ref "U5") (pin "57") (pinfunction "PA24/MCDA3/PCK1/AD6_57") (pintype "bidirectional"))
    )
    (net (code "21") (name "/MISO") (class "Default")
      (node (ref "JP5") (pin "6") (pinfunction "6_6") (pintype "passive"))
      (node (ref "U5") (pin "75") (pinfunction "PA25/SPI0_MISO/A18_75") (pintype "bidirectional"))
    )
    (net (code "22") (name "/MOSI") (class "Default")
      (node (ref "JP5") (pin "3") (pinfunction "3_3") (pintype "passive"))
      (node (ref "U5") (pin "76") (pinfunction "PA26/SPI0_MOSI/A19_76") (pintype "bidirectional"))
    )
    (net (code "23") (name "/PA2") (class "Default")
      (node (ref "J6") (pin "12") (pinfunction "12_12") (pintype "passive"))
      (node (ref "U5") (pin "63") (pinfunction "PA2/TIOA1/NANDRDY/AD0_63") (pintype "bidirectional"))
    )
    (net (code "24") (name "/PA3") (class "Default")
      (node (ref "J6") (pin "11") (pinfunction "11_11") (pintype "passive"))
      (node (ref "U5") (pin "62") (pinfunction "PA3/TIOB1/PWMFI0/WKUP1_62") (pintype "bidirectional"))
    )
    (net (code "25") (name "/PA4") (class "Default")
      (node (ref "J6") (pin "14") (pinfunction "14_14") (pintype "passive"))
      (node (ref "U5") (pin "61") (pinfunction "PA4/TCLK1/NWAIT/AD2_61") (pintype "bidirectional"))
    )
    (net (code "26") (name "/PA15") (class "Default")
      (node (ref "U5") (pin "8") (pinfunction "PA15/CTS1/TF/WKUP8_8") (pintype "bidirectional"))
    )
    (net (code "27") (name "/PA17") (class "Default")
      (node (ref "U5") (pin "9") (pinfunction "PA17/TWD0/SPCK0_9") (pintype "bidirectional"))
    )
    (net (code "28") (name "/PA28") (class "Default")
      (node (ref "J6") (pin "5") (pinfunction "5_5") (pintype "passive"))
      (node (ref "U5") (pin "78") (pinfunction "PA28/SPI0_NPCS0/PCK2/WKUP11_78") (pintype "bidirectional"))
    )
    (net (code "29") (name "/PA29") (class "Default")
      (node (ref "J6") (pin "4") (pinfunction "4_4") (pintype "passive"))
      (node (ref "U5") (pin "79") (pinfunction "PA29/SPI0_NPCS1/NRD_79") (pintype "bidirectional"))
    )
    (net (code "30") (name "/PB12") (class "Default")
      (node (ref "J6") (pin "9") (pinfunction "9_9") (pintype "passive"))
      (node (ref "U5") (pin "64") (pinfunction "PB12/TWD1/PWMH0/AD8_64") (pintype "bidirectional"))
    )
    (net (code "31") (name "/PB13") (class "Default")
      (node (ref "J6") (pin "10") (pinfunction "10_10") (pintype "passive"))
      (node (ref "U5") (pin "65") (pinfunction "PB13/TWCK1/PWMH1/AD9_65") (pintype "bidirectional"))
    )
    (net (code "32") (name "/PB17") (class "Default")
      (node (ref "J6") (pin "8") (pinfunction "8_8") (pintype "passive"))
      (node (ref "U5") (pin "66") (pinfunction "PB17/RF/PWML1/AD10_66") (pintype "bidirectional"))
    )
    (net (code "33") (name "/PB18") (class "Default")
      (node (ref "J6") (pin "6") (pinfunction "6_6") (pintype "passive"))
      (node (ref "U5") (pin "67") (pinfunction "PB18/RD/PWML2/AD11_67") (pintype "bidirectional"))
    )
    (net (code "34") (name "/PB19") (class "Default")
      (node (ref "J6") (pin "7") (pinfunction "7_7") (pintype "passive"))
      (node (ref "U5") (pin "68") (pinfunction "PB19/RK/PWML3/AD12_68") (pintype "bidirectional"))
    )
    (net (code "35") (name "/SCLK") (class "Default")
      (node (ref "JP5") (pin "4") (pinfunction "4_4") (pintype "passive"))
      (node (ref "U5") (pin "77") (pinfunction "PA27/SPI0_SPCK/A20/WKUP10_77") (pintype "bidirectional"))
    )
    (net (code "36") (name "/SDCD") (class "Default")
      (node (ref "J8") (pin "CD2") (pinfunction "CD2_CD2") (pintype "bidirectional"))
      (node (ref "U5") (pin "48") (pinfunction "PA18/TWCK0/A20/WKUP9_48") (pintype "bidirectional"))
    )
    (net (code "37") (name "/USB_DN") (class "Default")
      (node (ref "J9") (pin "D-") (pinfunction "D-_D-") (pintype "bidirectional"))
      (node (ref "R10") (pin "1") (pinfunction "1_1") (pintype "passive"))
      (node (ref "U5") (pin "27") (pinfunction "DHSDM_27") (pintype "bidirectional"))
      (node (ref "U6") (pin "3") (pinfunction "IO2_3") (pintype "bidirectional"))
    )
    (net (code "38") (name "/USB_DP") (class "Default")
      (node (ref "J9") (pin "D+") (pinfunction "D+_D+") (pintype "bidirectional"))
      (node (ref "R11") (pin "1") (pinfunction "1_1") (pintype "passive"))
      (node (ref "U5") (pin "26") (pinfunction "DHSDP_26") (pintype "bidirectional"))
      (node (ref "U6") (pin "2") (pinfunction "IO1_2") (pintype "bidirectional"))
    )
    (net (code "39") (name "/VBUS") (class "Default")
      (node (ref "C41") (pin "2") (pinfunction "2_2") (pintype "passive"))
      (node (ref "J9") (pin "VBUS") (pinfunction "VBUS_VBUS") (pintype "bidirectional"))
      (node (ref "U5") (pin "28") (pinfunction "VBUS_28") (pintype "power_in"))
      (node (ref "U6") (pin "4") (pinfunction "VCC_4") (pintype "power_in"))
    )
    (net (code "40") (name "/VDDANA") (class "Default")
      (node (ref "C10") (pin "1") (pinfunction "1_1") (pintype "passive"))
      (node (ref "C6") (pin "1") (pinfunction "1_1") (pintype "passive"))
      (node (ref "L1") (pin "2") (pinfunction "2_2") (pintype "passive"))
      (node (ref "U5") (pin "51") (pinfunction "VDDANA_51") (pintype "power_in"))
    )
    (net (code "41") (name "/VDDPLL") (class "Default")
      (node (ref "C11") (pin "1") (pinfunction "1_1") (pintype "passive"))
      (node (ref "C7") (pin "1") (pinfunction "1_1") (pintype "passive"))
      (node (ref "L2") (pin "2") (pinfunction "2_2") (pintype "passive"))
      (node (ref "U5") (pin "23") (pinfunction "VDDPLL_23") (pintype "input"))
    )
    (net (code "42") (name "/VDDUTMI") (class "Default")
      (node (ref "C21") (pin "1") (pinfunction "1_1") (pintype "passive"))
      (node (ref "C24") (pin "1") (pinfunction "1_1") (pintype "passive"))
      (node (ref "L3") (pin "2") (pinfunction "2_2") (pintype "passive"))
      (node (ref "U5") (pin "30") (pinfunction "VDDUTMI_30") (pintype "input"))
    )
    (net (code "43") (name "/X-DIR") (class "Default")
      (node (ref "P1") (pin "DIR") (pinfunction "DIR_DIR") (pintype "bidirectional"))
      (node (ref "U5") (pin "5") (pinfunction "PA12/RXD1/PWML1/WKUP7_5") (pintype "bidirectional"))
    )
    (net (code "44") (name "/X-STEP") (class "Default")
      (node (ref "P1") (pin "STEP") (pinfunction "STEP_STEP") (pintype "bidirectional"))
      (node (ref "U5") (pin "6") (pinfunction "PA13/TXD1/PWMH2_6") (pintype "bidirectional"))
    )
    (net (code "45") (name "/X-STOP") (class "Default")
      (node (ref "JP8") (pin "1") (pinfunction "1_1") (pintype "passive"))
      (node (ref "U5") (pin "54") (pinfunction "PB15/CANRX1/PWMH3/DAC0_54") (pintype "bidirectional"))
    )
    (net (code "46") (name "/XTAL1") (class "Default")
      (node (ref "C35") (pin "2") (pinfunction "2_2") (pintype "passive"))
      (node (ref "U5") (pin "25") (pinfunction "XIN_25") (pintype "input"))
      (node (ref "X1") (pin "P$2") (pinfunction "2_P$2") (pintype "passive"))
    )
    (net (code "47") (name "/XTAL2") (class "Default")
      (node (ref "C34") (pin "2") (pinfunction "2_2") (pintype "passive"))
      (node (ref "U5") (pin "24") (pinfunction "XOUT_24") (pintype "output"))
      (node (ref "X1") (pin "P$1") (pinfunction "1_P$1") (pintype "passive"))
    )
    (net (code "48") (name "/Y-DIR") (class "Default")
      (node (ref "P2") (pin "DIR") (pinfunction "DIR_DIR") (pintype "bidirectional"))
      (node (ref "U5") (pin "2") (pinfunction "PA9/UTXD/PWMH3_2") (pintype "bidirectional"))
    )
    (net (code "49") (name "/Y-STEP") (class "Default")
      (node (ref "P2") (pin "STEP") (pinfunction "STEP_STEP") (pintype "bidirectional"))
      (node (ref "U5") (pin "3") (pinfunction "PA10/RXD0/DATRG/WKUP5_3") (pintype "bidirectional"))
    )
    (net (code "50") (name "/Y-STOP") (class "Default")
      (node (ref "JP9") (pin "1") (pinfunction "1_1") (pintype "passive"))
      (node (ref "U5") (pin "16") (pinfunction "PA7/TCLK2/NCS1/WKUP3_16") (pintype "bidirectional"))
    )
    (net (code "51") (name "/Z-DIR") (class "Default")
      (node (ref "P3") (pin "DIR") (pinfunction "DIR_DIR") (pintype "bidirectional"))
      (node (ref "U5") (pin "99") (pinfunction "PB24/SCK2/NCS2_99") (pintype "bidirectional"))
    )
    (net (code "52") (name "/Z-STEP") (class "Default")
      (node (ref "P3") (pin "STEP") (pinfunction "STEP_STEP") (pintype "bidirectional"))
      (node (ref "U5") (pin "100") (pinfunction "PB25/RTS0/TIOA0_100") (pintype "bidirectional"))
    )
    (net (code "53") (name "/Z-STOP") (class "Default")
      (node (ref "Q4") (pin "3") (pinfunction "C_3") (pintype "passive"))
      (node (ref "U5") (pin "17") (pinfunction "PA8/URXD/PWMH0/WKUP4_17") (pintype "bidirectional"))
    )
    (net (code "54") (name "/~{E1-ENABLE}") (class "Default")
      (node (ref "P4") (pin "!EN") (pinfunction "~{ENABLE}_!EN") (pintype "input"))
      (node (ref "R22") (pin "2") (pinfunction "2_2") (pintype "passive"))
      (node (ref "U5") (pin "98") (pinfunction "PB23/CTS2.SPI0_NPCS3/WKUP14_98") (pintype "bidirectional"))
    )
    (net (code "55") (name "/~{HOTBED}") (class "Default")
      (node (ref "R15") (pin "1") (pinfunction "1_1") (pintype "passive"))
      (node (ref "U3") (pin "3") (pinfunction "IN_3") (pintype "input"))
      (node (ref "U5") (pin "15") (pinfunction "PA5/TIOA2/PWMFI0/WKUP2_15") (pintype "bidirectional"))
    )
    (net (code "56") (name "/~{HOTEND-1}") (class "Default")
      (node (ref "R4") (pin "1") (pinfunction "1_1") (pintype "passive"))
      (node (ref "U1") (pin "3") (pinfunction "IN_3") (pintype "input"))
      (node (ref "U5") (pin "14") (pinfunction "PA1/CANRX0/PCK0/WKUP0_14") (pintype "bidirectional"))
    )
    (net (code "57") (name "/~{PWM-FAN}") (class "Default")
      (node (ref "R2") (pin "1") (pinfunction "1_1") (pintype "passive"))
      (node (ref "R3") (pin "1") (pinfunction "1_1") (pintype "passive"))
      (node (ref "U5") (pin "85") (pinfunction "PB5/TIOB5_85") (pintype "bidirectional"))
    )
    (net (code "58") (name "/~{RESET}") (class "Default")
      (node (ref "JP4") (pin "10") (pinfunction "10_10") (pintype "passive"))
      (node (ref "JP5") (pin "2") (pinfunction "2_2") (pintype "passive"))
      (node (ref "S1") (pin "1") (pinfunction "1_1") (pintype "passive"))
      (node (ref "U5") (pin "47") (pinfunction "~{NRST}_47") (pintype "bidirectional"))
    )
    (net (code "59") (name "/~{X-ENABLE}") (class "Default")
      (node (ref "P1") (pin "!EN") (pinfunction "~{ENABLE}_!EN") (pintype "input"))
      (node (ref "R20") (pin "2") (pinfunction "2_2") (pintype "passive"))
      (node (ref "U5") (pin "7") (pinfunction "PA14/RTS1/TK_7") (pintype "bidirectional"))
    )
    (net (code "60") (name "/~{Y-ENABLE}") (class "Default")
      (node (ref "P2") (pin "!EN") (pinfunction "~{ENABLE}_!EN") (pintype "input"))
      (node (ref "R19") (pin "2") (pinfunction "2_2") (pintype "passive"))
      (node (ref "U5") (pin "4") (pinfunction "PA11/TXD0/ADTRG/WKUP6_4") (pintype "bidirectional"))
    )
    (net (code "61") (name "/~{Z-ENABLE}") (class "Default")
      (node (ref "P3") (pin "!EN") (pinfunction "~{ENABLE}_!EN") (pintype "input"))
      (node (ref "R21") (pin "2") (pinfunction "2_2") (pintype "passive"))
      (node (ref "U5") (pin "1") (pinfunction "PB26/CTS0/TCLK0/WKUP15_1") (pintype "bidirectional"))
    )
    (net (code "62") (name "24V") (class "Default")
      (node (ref "C20") (pin "1") (pinfunction "1_1") (pintype "passive"))
      (node (ref "C29") (pin "+") (pinfunction "+_+") (pintype "passive"))
      (node (ref "C33") (pin "1") (pinfunction "1_1") (pintype "passive"))
      (node (ref "C37") (pin "+") (pinfunction "+_+") (pintype "passive"))
      (node (ref "C46") (pin "+") (pinfunction "+_+") (pintype "passive"))
      (node (ref "C47") (pin "+") (pinfunction "+_+") (pintype "passive"))
      (node (ref "C48") (pin "+") (pinfunction "+_+") (pintype "passive"))
      (node (ref "C49") (pin "+") (pinfunction "+_+") (pintype "passive"))
      (node (ref "F1") (pin "P$3") (pinfunction "P$3_P$3") (pintype "passive"))
      (node (ref "F1") (pin "P$4") (pinfunction "P$4_P$4") (pintype "passive"))
      (node (ref "J2") (pin "1") (pinfunction "1_1") (pintype "passive"))
      (node (ref "J3") (pin "1") (pinfunction "1_1") (pintype "passive"))
      (node (ref "J4") (pin "1") (pinfunction "1_1") (pintype "passive"))
      (node (ref "J5") (pin "3") (pinfunction "3_3") (pintype "power_in"))
      (node (ref "J5") (pin "4") (pinfunction "4_4") (pintype "power_in"))
      (node (ref "J6") (pin "3") (pinfunction "3_3") (pintype "passive"))
      (node (ref "J7") (pin "3") (pinfunction "3_3") (pintype "power_in"))
      (node (ref "J7") (pin "4") (pinfunction "4_4") (pintype "power_in"))
      (node (ref "JP6") (pin "1") (pinfunction "1_1") (pintype "passive"))
      (node (ref "JP7") (pin "4") (pinfunction "4_4") (pintype "passive"))
      (node (ref "P1") (pin "VMOT") (pinfunction "VMOT_VMOT") (pintype "power_in"))
      (node (ref "P2") (pin "VMOT") (pinfunction "VMOT_VMOT") (pintype "power_in"))
      (node (ref "P3") (pin "VMOT") (pinfunction "VMOT_VMOT") (pintype "power_in"))
      (node (ref "P4") (pin "VMOT") (pinfunction "VMOT_VMOT") (pintype "power_in"))
      (node (ref "R5") (pin "1") (pinfunction "1_1") (pintype "passive"))
      (node (ref "U2") (pin "5") (pinfunction "VIN_5") (pintype "power_in"))
      (node (ref "U4") (pin "3") (pinfunction "VIN_3") (pintype "power_in"))
    )
    (net (code "63") (name "GND") (class "Default")
      (node (ref "C1") (pin "2") (pinfunction "2_2") (pintype "passive"))
      (node (ref "C10") (pin "2") (pinfunction "2_2") (pintype "passive"))
      (node (ref "C11") (pin "2") (pinfunction "2_2") (pintype "passive"))
      (node (ref "C12") (pin "2") (pinfunction "2_2") (pintype "passive"))
      (node (ref "C13") (pin "2") (pinfunction "2_2") (pintype "passive"))
      (node (ref "C14") (pin "2") (pinfunction "2_2") (pintype "passive"))
      (node (ref "C15") (pin "2") (pinfunction "2_2") (pintype "passive"))
      (node (ref "C16") (pin "2") (pinfunction "2_2") (pintype "passive"))
      (node (ref "C17") (pin "2") (pinfunction "2_2") (pintype "passive"))
      (node (ref "C18") (pin "2") (pinfunction "2_2") (pintype "passive"))
      (node (ref "C19") (pin "2") (pinfunction "2_2") (pintype "passive"))
      (node (ref "C2") (pin "2") (pinfunction "2_2") (pintype "passive"))
      (node (ref "C20") (pin "2") (pinfunction "2_2") (pintype "passive"))
      (node (ref "C21") (pin "2") (pinfunction "2_2") (pintype "passive"))
      (node (ref "C22") (pin "2") (pinfunction "2_2") (pintype "passive"))
      (node (ref "C23") (pin "2") (pinfunction "2_2") (pintype "passive"))
      (node (ref "C24") (pin "2") (pinfunction "2_2") (pintype "passive"))
      (node (ref "C25") (pin "2") (pinfunction "2_2") (pintype "passive"))
      (node (ref "C26") (pin "2") (pinfunction "2_2") (pintype "passive"))
      (node (ref "C27") (pin "2") (pinfunction "2_2") (pintype "passive"))
      (node (ref "C29") (pin "-") (pinfunction "-_-") (pintype "passive"))
      (node (ref "C3") (pin "2") (pinfunction "2_2") (pintype "passive"))
      (node (ref "C30") (pin "2") (pinfunction "2_2") (pintype "passive"))
      (node (ref "C31") (pin "2") (pinfunction "2_2") (pintype "passive"))
      (node (ref "C32") (pin "2") (pinfunction "2_2") (pintype "passive"))
      (node (ref "C33") (pin "2") (pinfunction "2_2") (pintype "passive"))
      (node (ref "C34") (pin "1") (pinfunction "1_1") (pintype "passive"))
      (node (ref "C35") (pin "1") (pinfunction "1_1") (pintype "passive"))
      (node (ref "C36") (pin "2") (pinfunction "2_2") (pintype "passive"))
      (node (ref "C37") (pin "-") (pinfunction "-_-") (pintype "passive"))
      (node (ref "C38") (pin "2") (pinfunction "2_2") (pintype "passive"))
      (node (ref "C39") (pin "1") (pinfunction "1_1") (pintype "passive"))
      (node (ref "C4") (pin "2") (pinfunction "2_2") (pintype "passive"))
      (node (ref "C40") (pin "1") (pinfunction "1_1") (pintype "passive"))
      (node (ref "C41") (pin "1") (pinfunction "1_1") (pintype "passive"))
      (node (ref "C42") (pin "1") (pinfunction "1_1") (pintype "passive"))
      (node (ref "C43") (pin "1") (pinfunction "1_1") (pintype "passive"))
      (node (ref "C44") (pin "1") (pinfunction "1_1") (pintype "passive"))
      (node (ref "C45") (pin "1") (pinfunction "1_1") (pintype "passive"))
      (node (ref "C46") (pin "-") (pinfunction "-_-") (pintype "passive"))
      (node (ref "C47") (pin "-") (pinfunction "-_-") (pintype "passive"))
      (node (ref "C48") (pin "-") (pinfunction "-_-") (pintype "passive"))
      (node (ref "C49") (pin "-") (pinfunction "-_-") (pintype "passive"))
      (node (ref "C5") (pin "2") (pinfunction "2_2") (pintype "passive"))
      (node (ref "C6") (pin "2") (pinfunction "2_2") (pintype "passive"))
      (node (ref "C7") (pin "2") (pinfunction "2_2") (pintype "passive"))
      (node (ref "C8") (pin "2") (pinfunction "2_2") (pintype "passive"))
      (node (ref "C9") (pin "2") (pinfunction "2_2") (pintype "passive"))
      (node (ref "D1") (pin "A") (pinfunction "A_A") (pintype "passive"))
      (node (ref "D2") (pin "A") (pinfunction "A_A") (pintype "passive"))
      (node (ref "J1") (pin "3") (pinfunction "3_3") (pintype "power_in"))
      (node (ref "J1") (pin "4") (pinfunction "4_4") (pintype "power_in"))
      (node (ref "J10") (pin "2") (pinfunction "2_2") (pintype "passive"))
      (node (ref "J11") (pin "2") (pinfunction "2_2") (pintype "passive"))
      (node (ref "J2") (pin "2") (pinfunction "2_2") (pintype "passive"))
      (node (ref "J3") (pin "2") (pinfunction "2_2") (pintype "passive"))
      (node (ref "J6") (pin "1") (pinfunction "1_1") (pintype "passive"))
      (node (ref "J8") (pin "6") (pinfunction "GND_6") (pintype "power_in"))
      (node (ref "J8") (pin "C1") (pinfunction "SHEILD_C1") (pintype "bidirectional"))
      (node (ref "J8") (pin "C2") (pinfunction "SHIELD_C2") (pintype "bidirectional"))
      (node (ref "J8") (pin "C3") (pinfunction "SHIELD_C3") (pintype "bidirectional"))
      (node (ref "J8") (pin "C4") (pinfunction "SHIELD_C4") (pintype "bidirectional"))
      (node (ref "J8") (pin "CD1") (pinfunction "CD1_CD1") (pintype "bidirectional"))
      (node (ref "J9") (pin "GND") (pinfunction "GND_GND") (pintype "bidirectional"))
      (node (ref "J9") (pin "GND1") (pinfunction "GND_GND1") (pintype "bidirectional"))
      (node (ref "J9") (pin "GND2") (pinfunction "GND_GND2") (pintype "bidirectional"))
      (node (ref "J9") (pin "GND3") (pinfunction "GND_GND3") (pintype "bidirectional"))
      (node (ref "J9") (pin "GND4") (pinfunction "GND_GND4") (pintype "bidirectional"))
      (node (ref "J9") (pin "GND5") (pinfunction "GND_GND5") (pintype "bidirectional"))
      (node (ref "J9") (pin "GND6") (pinfunction "GND_GND6") (pintype "bidirectional"))
      (node (ref "J9") (pin "GND7") (pinfunction "GND_GND7") (pintype "bidirectional"))
      (node (ref "J9") (pin "GND8") (pinfunction "GND_GND8") (pintype "bidirectional"))
      (node (ref "JP10") (pin "3") (pinfunction "3_3") (pintype "passive"))
      (node (ref "JP4") (pin "3") (pinfunction "3_3") (pintype "passive"))
      (node (ref "JP4") (pin "5") (pinfunction "5_5") (pintype "passive"))
      (node (ref "JP4") (pin "9") (pinfunction "9_9") (pintype "passive"))
      (node (ref "JP5") (pin "1") (pinfunction "1_1") (pintype "passive"))
      (node (ref "JP7") (pin "3") (pinfunction "3_3") (pintype "passive"))
      (node (ref "JP8") (pin "3") (pinfunction "3_3") (pintype "passive"))
      (node (ref "JP9") (pin "3") (pinfunction "3_3") (pintype "passive"))
      (node (ref "LED1") (pin "C") (pinfunction "C_C") (pintype "passive"))
      (node (ref "P1") (pin "GNDMOT") (pinfunction "GNDMOT_GNDMOT") (pintype "power_in"))
      (node (ref "P1") (pin "GNDVDD") (pinfunction "GNDVDD_GNDVDD") (pintype "power_in"))
      (node (ref "P2") (pin "GNDMOT") (pinfunction "GNDMOT_GNDMOT") (pintype "power_in"))
      (node (ref "P2") (pin "GNDVDD") (pinfunction "GNDVDD_GNDVDD") (pintype "power_in"))
      (node (ref "P3") (pin "GNDMOT") (pinfunction "GNDMOT_GNDMOT") (pintype "power_in"))
      (node (ref "P3") (pin "GNDVDD") (pinfunction "GNDVDD_GNDVDD") (pintype "power_in"))
      (node (ref "P4") (pin "GNDMOT") (pinfunction "GNDMOT_GNDMOT") (pintype "power_in"))
      (node (ref "P4") (pin "GNDVDD") (pinfunction "GNDVDD_GNDVDD") (pintype "power_in"))
      (node (ref "Q1") (pin "2") (pinfunction "S_2") (pintype "passive"))
      (node (ref "Q2") (pin "1") (pinfunction "S1_1") (pintype "passive"))
      (node (ref "Q2") (pin "2") (pinfunction "S2_2") (pintype "passive"))
      (node (ref "Q2") (pin "3") (pinfunction "S3_3") (pintype "passive"))
      (node (ref "Q3") (pin "1") (pinfunction "S1_1") (pintype "passive"))
      (node (ref "Q3") (pin "2") (pinfunction "S2_2") (pintype "passive"))
      (node (ref "Q3") (pin "3") (pinfunction "S3_3") (pintype "passive"))
      (node (ref "Q4") (pin "2") (pinfunction "E_2") (pintype "passive"))
      (node (ref "R12") (pin "2") (pinfunction "2_2") (pintype "passive"))
      (node (ref "R14") (pin "2") (pinfunction "2_2") (pintype "passive"))
      (node (ref "R15") (pin "2") (pinfunction "2_2") (pintype "passive"))
      (node (ref "R2") (pin "2") (pinfunction "2_2") (pintype "passive"))
      (node (ref "R4") (pin "2") (pinfunction "2_2") (pintype "passive"))
      (node (ref "R6") (pin "2") (pinfunction "2_2") (pintype "passive"))
      (node (ref "R8") (pin "1") (pinfunction "1_1") (pintype "passive"))
      (node (ref "S1") (pin "3") (pinfunction "3_3") (pintype "passive"))
      (node (ref "S1") (pin "4") (pinfunction "4_4") (pintype "passive"))
      (node (ref "SCREW1") (pin "GND") (pinfunction "P$1_GND") (pintype "bidirectional"))
      (node (ref "SCREW2") (pin "GND") (pinfunction "P$1_GND") (pintype "bidirectional"))
      (node (ref "SCREW3") (pin "GND") (pinfunction "P$1_GND") (pintype "bidirectional"))
      (node (ref "SCREW4") (pin "GND") (pinfunction "P$1_GND") (pintype "bidirectional"))
      (node (ref "U1") (pin "1") (pinfunction "GND1_1") (pintype "passive"))
      (node (ref "U1") (pin "4") (pinfunction "GND2_4") (pintype "passive"))
      (node (ref "U2") (pin "2") (pinfunction "GND_2") (pintype "power_in"))
      (node (ref "U3") (pin "1") (pinfunction "GND1_1") (pintype "passive"))
      (node (ref "U3") (pin "4") (pinfunction "GND2_4") (pintype "passive"))
      (node (ref "U4") (pin "2") (pinfunction "GND_2") (pintype "passive"))
      (node (ref "U5") (pin "12") (pinfunction "GND1_12") (pintype "power_in"))
      (node (ref "U5") (pin "22") (pinfunction "GNDPLL_22") (pintype "power_in"))
      (node (ref "U5") (pin "33") (pinfunction "GNDUTMI_33") (pintype "power_in"))
      (node (ref "U5") (pin "35") (pinfunction "JTAGSEL_35") (pintype "input"))
      (node (ref "U5") (pin "41") (pinfunction "GND2_41") (pintype "power_in"))
      (node (ref "U5") (pin "44") (pinfunction "GND3_44") (pintype "power_in"))
      (node (ref "U5") (pin "52") (pinfunction "GNDANA_52") (pintype "power_in"))
      (node (ref "U5") (pin "73") (pinfunction "GND4_73") (pintype "power_in"))
      (node (ref "U5") (pin "91") (pinfunction "GND5_91") (pintype "power_in"))
      (node (ref "U6") (pin "1") (pinfunction "GND_1") (pintype "power_in"))
    )
    (net (code "64") (name "Net-(F1-PadP$1)") (class "Default")
      (node (ref "F1") (pin "P$1") (pinfunction "P$1_P$1") (pintype "passive"))
      (node (ref "F1") (pin "P$2") (pinfunction "P$2_P$2") (pintype "passive"))
      (node (ref "J1") (pin "1") (pinfunction "1_1") (pintype "power_in"))
      (node (ref "J1") (pin "2") (pinfunction "2_2") (pintype "power_in"))
    )
    (net (code "65") (name "Net-(F2-PadP$2)") (class "Default")
      (node (ref "F2") (pin "P$2") (pinfunction "P$2_P$2") (pintype "passive"))
      (node (ref "J4") (pin "2") (pinfunction "2_2") (pintype "passive"))
    )
    (net (code "66") (name "Net-(JP10-Pad2)") (class "Default")
      (node (ref "JP10") (pin "2") (pinfunction "2_2") (pintype "passive"))
      (node (ref "JP6") (pin "2") (pinfunction "2_2") (pintype "passive"))
      (node (ref "JP8") (pin "2") (pinfunction "2_2") (pintype "passive"))
      (node (ref "JP9") (pin "2") (pinfunction "2_2") (pintype "passive"))
    )
    (net (code "67") (name "Net-(LED1-PadA)") (class "Default")
      (node (ref "LED1") (pin "A") (pinfunction "A_A") (pintype "passive"))
      (node (ref "R1") (pin "1") (pinfunction "1_1") (pintype "passive"))
    )
    (net (code "68") (name "Net-(P1-MOT-1A)") (class "Default")
      (node (ref "JP11") (pin "3") (pinfunction "3_3") (pintype "passive"))
      (node (ref "P1") (pin "1A") (pinfunction "MOT-1A_1A") (pintype "power_in"))
    )
    (net (code "69") (name "Net-(P1-MOT-1B)") (class "Default")
      (node (ref "JP11") (pin "4") (pinfunction "4_4") (pintype "passive"))
      (node (ref "P1") (pin "1B") (pinfunction "MOT-1B_1B") (pintype "power_in"))
    )
    (net (code "70") (name "Net-(P1-MOT-2A)") (class "Default")
      (node (ref "JP11") (pin "2") (pinfunction "2_2") (pintype "passive"))
      (node (ref "P1") (pin "2A") (pinfunction "MOT-2A_2A") (pintype "power_in"))
    )
    (net (code "71") (name "Net-(P1-MOT-2B)") (class "Default")
      (node (ref "JP11") (pin "1") (pinfunction "1_1") (pintype "passive"))
      (node (ref "P1") (pin "2B") (pinfunction "MOT-2B_2B") (pintype "power_in"))
    )
    (net (code "72") (name "Net-(P1-PadMS1)") (class "Default")
      (node (ref "P1") (pin "MS1") (pinfunction "MS1_MS1") (pintype "input"))
      (node (ref "SJ9") (pin "1") (pinfunction "1_1") (pintype "passive"))
    )
    (net (code "73") (name "Net-(P1-PadMS2)") (class "Default")
      (node (ref "P1") (pin "MS2") (pinfunction "MS2_MS2") (pintype "input"))
      (node (ref "SJ5") (pin "1") (pinfunction "1_1") (pintype "passive"))
    )
    (net (code "74") (name "Net-(P1-PadMS3)") (class "Default")
      (node (ref "P1") (pin "MS3") (pinfunction "MS3_MS3") (pintype "input"))
      (node (ref "SJ1") (pin "1") (pinfunction "1_1") (pintype "passive"))
    )
    (net (code "75") (name "Net-(P1-~{RESET})") (class "Default")
      (node (ref "P1") (pin "!RST") (pinfunction "~{RESET}_!RST") (pintype "input"))
      (node (ref "P1") (pin "!SLP") (pinfunction "~{SLEEP}_!SLP") (pintype "input"))
    )
    (net (code "76") (name "Net-(P2-MOT-1A)") (class "Default")
      (node (ref "JP12") (pin "3") (pinfunction "3_3") (pintype "passive"))
      (node (ref "P2") (pin "1A") (pinfunction "MOT-1A_1A") (pintype "power_in"))
    )
    (net (code "77") (name "Net-(P2-MOT-1B)") (class "Default")
      (node (ref "JP12") (pin "4") (pinfunction "4_4") (pintype "passive"))
      (node (ref "P2") (pin "1B") (pinfunction "MOT-1B_1B") (pintype "power_in"))
    )
    (net (code "78") (name "Net-(P2-MOT-2A)") (class "Default")
      (node (ref "JP12") (pin "2") (pinfunction "2_2") (pintype "passive"))
      (node (ref "P2") (pin "2A") (pinfunction "MOT-2A_2A") (pintype "power_in"))
    )
    (net (code "79") (name "Net-(P2-MOT-2B)") (class "Default")
      (node (ref "JP12") (pin "1") (pinfunction "1_1") (pintype "passive"))
      (node (ref "P2") (pin "2B") (pinfunction "MOT-2B_2B") (pintype "power_in"))
    )
    (net (code "80") (name "Net-(P2-PadMS1)") (class "Default")
      (node (ref "P2") (pin "MS1") (pinfunction "MS1_MS1") (pintype "input"))
      (node (ref "SJ10") (pin "1") (pinfunction "1_1") (pintype "passive"))
    )
    (net (code "81") (name "Net-(P2-PadMS2)") (class "Default")
      (node (ref "P2") (pin "MS2") (pinfunction "MS2_MS2") (pintype "input"))
      (node (ref "SJ6") (pin "1") (pinfunction "1_1") (pintype "passive"))
    )
    (net (code "82") (name "Net-(P2-PadMS3)") (class "Default")
      (node (ref "P2") (pin "MS3") (pinfunction "MS3_MS3") (pintype "input"))
      (node (ref "SJ2") (pin "1") (pinfunction "1_1") (pintype "passive"))
    )
    (net (code "83") (name "Net-(P2-~{RESET})") (class "Default")
      (node (ref "P2") (pin "!RST") (pinfunction "~{RESET}_!RST") (pintype "input"))
      (node (ref "P2") (pin "!SLP") (pinfunction "~{SLEEP}_!SLP") (pintype "input"))
    )
    (net (code "84") (name "Net-(P3-MOT-1A)") (class "Default")
      (node (ref "JP14") (pin "3") (pinfunction "3_3") (pintype "passive"))
      (node (ref "P3") (pin "1A") (pinfunction "MOT-1A_1A") (pintype "power_in"))
    )
    (net (code "85") (name "Net-(P3-MOT-1B)") (class "Default")
      (node (ref "JP14") (pin "4") (pinfunction "4_4") (pintype "passive"))
      (node (ref "P3") (pin "1B") (pinfunction "MOT-1B_1B") (pintype "power_in"))
    )
    (net (code "86") (name "Net-(P3-MOT-2A)") (class "Default")
      (node (ref "JP14") (pin "2") (pinfunction "2_2") (pintype "passive"))
      (node (ref "P3") (pin "2A") (pinfunction "MOT-2A_2A") (pintype "power_in"))
    )
    (net (code "87") (name "Net-(P3-MOT-2B)") (class "Default")
      (node (ref "JP14") (pin "1") (pinfunction "1_1") (pintype "passive"))
      (node (ref "P3") (pin "2B") (pinfunction "MOT-2B_2B") (pintype "power_in"))
    )
    (net (code "88") (name "Net-(P3-PadMS1)") (class "Default")
      (node (ref "P3") (pin "MS1") (pinfunction "MS1_MS1") (pintype "input"))
      (node (ref "SJ11") (pin "1") (pinfunction "1_1") (pintype "passive"))
    )
    (net (code "89") (name "Net-(P3-PadMS2)") (class "Default")
      (node (ref "P3") (pin "MS2") (pinfunction "MS2_MS2") (pintype "input"))
      (node (ref "SJ7") (pin "1") (pinfunction "1_1") (pintype "passive"))
    )
    (net (code "90") (name "Net-(P3-PadMS3)") (class "Default")
      (node (ref "P3") (pin "MS3") (pinfunction "MS3_MS3") (pintype "input"))
      (node (ref "SJ3") (pin "1") (pinfunction "1_1") (pintype "passive"))
    )
    (net (code "91") (name "Net-(P3-~{RESET})") (class "Default")
      (node (ref "P3") (pin "!RST") (pinfunction "~{RESET}_!RST") (pintype "input"))
      (node (ref "P3") (pin "!SLP") (pinfunction "~{SLEEP}_!SLP") (pintype "input"))
    )
    (net (code "92") (name "Net-(P4-MOT-1A)") (class "Default")
      (node (ref "JP13") (pin "3") (pinfunction "3_3") (pintype "passive"))
      (node (ref "P4") (pin "1A") (pinfunction "MOT-1A_1A") (pintype "power_in"))
    )
    (net (code "93") (name "Net-(P4-MOT-1B)") (class "Default")
      (node (ref "JP13") (pin "4") (pinfunction "4_4") (pintype "passive"))
      (node (ref "P4") (pin "1B") (pinfunction "MOT-1B_1B") (pintype "power_in"))
    )
    (net (code "94") (name "Net-(P4-MOT-2A)") (class "Default")
      (node (ref "JP13") (pin "2") (pinfunction "2_2") (pintype "passive"))
      (node (ref "P4") (pin "2A") (pinfunction "MOT-2A_2A") (pintype "power_in"))
    )
    (net (code "95") (name "Net-(P4-MOT-2B)") (class "Default")
      (node (ref "JP13") (pin "1") (pinfunction "1_1") (pintype "passive"))
      (node (ref "P4") (pin "2B") (pinfunction "MOT-2B_2B") (pintype "power_in"))
    )
    (net (code "96") (name "Net-(P4-PadMS1)") (class "Default")
      (node (ref "P4") (pin "MS1") (pinfunction "MS1_MS1") (pintype "input"))
      (node (ref "SJ12") (pin "1") (pinfunction "1_1") (pintype "passive"))
    )
    (net (code "97") (name "Net-(P4-PadMS2)") (class "Default")
      (node (ref "P4") (pin "MS2") (pinfunction "MS2_MS2") (pintype "input"))
      (node (ref "SJ8") (pin "1") (pinfunction "1_1") (pintype "passive"))
    )
    (net (code "98") (name "Net-(P4-PadMS3)") (class "Default")
      (node (ref "P4") (pin "MS3") (pinfunction "MS3_MS3") (pintype "input"))
      (node (ref "SJ4") (pin "1") (pinfunction "1_1") (pintype "passive"))
    )
    (net (code "99") (name "Net-(P4-~{RESET})") (class "Default")
      (node (ref "P4") (pin "!RST") (pinfunction "~{RESET}_!RST") (pintype "input"))
      (node (ref "P4") (pin "!SLP") (pinfunction "~{SLEEP}_!SLP") (pintype "input"))
    )
    (net (code "100") (name "Net-(Q1-D)") (class "Default")
      (node (ref "D1") (pin "C") (pinfunction "C_C") (pintype "passive"))
      (node (ref "F2") (pin "P$1") (pinfunction "P$1_P$1") (pintype "passive"))
      (node (ref "Q1") (pin "3") (pinfunction "D_3") (pintype "passive"))
    )
    (net (code "101") (name "Net-(Q1-G)") (class "Default")
      (node (ref "Q1") (pin "1") (pinfunction "G_1") (pintype "passive"))
      (node (ref "R3") (pin "2") (pinfunction "2_2") (pintype "passive"))
    )
    (net (code "102") (name "Net-(Q2-D)") (class "Default")
      (node (ref "J5") (pin "1") (pinfunction "1_1") (pintype "power_in"))
      (node (ref "J5") (pin "2") (pinfunction "2_2") (pintype "power_in"))
      (node (ref "Q2") (pin "5-8") (pinfunction "D_5-8") (pintype "passive"))
    )
    (net (code "103") (name "Net-(Q2-G)") (class "Default")
      (node (ref "Q2") (pin "4") (pinfunction "G_4") (pintype "passive"))
      (node (ref "R7") (pin "2") (pinfunction "2_2") (pintype "passive"))
    )
    (net (code "104") (name "Net-(Q3-D)") (class "Default")
      (node (ref "J7") (pin "1") (pinfunction "1_1") (pintype "power_in"))
      (node (ref "J7") (pin "2") (pinfunction "2_2") (pintype "power_in"))
      (node (ref "Q3") (pin "5-8") (pinfunction "D_5-8") (pintype "passive"))
    )
    (net (code "105") (name "Net-(Q3-G)") (class "Default")
      (node (ref "Q3") (pin "4") (pinfunction "G_4") (pintype "passive"))
      (node (ref "R16") (pin "2") (pinfunction "2_2") (pintype "passive"))
    )
    (net (code "106") (name "Net-(Q4-B)") (class "Default")
      (node (ref "JP7") (pin "1") (pinfunction "1_1") (pintype "passive"))
      (node (ref "Q4") (pin "1") (pinfunction "B_1") (pintype "passive"))
    )
    (net (code "107") (name "Net-(U1-OUT)") (class "Default")
      (node (ref "R7") (pin "1") (pinfunction "1_1") (pintype "passive"))
      (node (ref "U1") (pin "5") (pinfunction "OUT_5") (pintype "passive"))
    )
    (net (code "108") (name "Net-(U2-CB)") (class "Default")
      (node (ref "C28") (pin "2") (pinfunction "2_2") (pintype "passive"))
      (node (ref "U2") (pin "1") (pinfunction "CB_1") (pintype "passive"))
    )
    (net (code "109") (name "Net-(U2-FB)") (class "Default")
      (node (ref "R13") (pin "2") (pinfunction "2_2") (pintype "passive"))
      (node (ref "R14") (pin "1") (pinfunction "1_1") (pintype "passive"))
      (node (ref "U2") (pin "3") (pinfunction "FB_3") (pintype "passive"))
    )
    (net (code "110") (name "Net-(U2-SW)") (class "Default")
      (node (ref "C28") (pin "1") (pinfunction "1_1") (pintype "passive"))
      (node (ref "D2") (pin "C") (pinfunction "C_C") (pintype "passive"))
      (node (ref "L5") (pin "1") (pinfunction "1_1") (pintype "passive"))
      (node (ref "U2") (pin "6") (pinfunction "SW_6") (pintype "passive"))
    )
    (net (code "111") (name "Net-(U2-~{SHDN})") (class "Default")
      (node (ref "R5") (pin "2") (pinfunction "2_2") (pintype "passive"))
      (node (ref "R6") (pin "1") (pinfunction "1_1") (pintype "passive"))
      (node (ref "U2") (pin "4") (pinfunction "~{SHDN}_4") (pintype "input"))
    )
    (net (code "112") (name "Net-(U3-OUT)") (class "Default")
      (node (ref "R16") (pin "1") (pinfunction "1_1") (pintype "passive"))
      (node (ref "U3") (pin "5") (pinfunction "OUT_5") (pintype "passive"))
    )
    (net (code "113") (name "Net-(U5C-DFSDM)") (class "Default")
      (node (ref "R10") (pin "2") (pinfunction "2_2") (pintype "passive"))
      (node (ref "U5") (pin "32") (pinfunction "DFSDM_32") (pintype "input"))
    )
    (net (code "114") (name "Net-(U5C-DFSDP)") (class "Default")
      (node (ref "R11") (pin "2") (pinfunction "2_2") (pintype "passive"))
      (node (ref "U5") (pin "31") (pinfunction "DFSDP_31") (pintype "input"))
    )
    (net (code "115") (name "Net-(U5C-FWUP)") (class "Default")
      (node (ref "R9") (pin "1") (pinfunction "1_1") (pintype "passive"))
      (node (ref "U5") (pin "40") (pinfunction "FWUP_40") (pintype "input"))
    )
    (net (code "116") (name "Net-(U5C-TST)") (class "Default")
      (node (ref "R12") (pin "1") (pinfunction "1_1") (pintype "passive"))
      (node (ref "U5") (pin "38") (pinfunction "TST_38") (pintype "input"))
    )
    (net (code "117") (name "Net-(U5C-VBG)") (class "Default")
      (node (ref "C27") (pin "1") (pinfunction "1_1") (pintype "passive"))
      (node (ref "R8") (pin "2") (pinfunction "2_2") (pintype "passive"))
      (node (ref "U5") (pin "29") (pinfunction "VBG_29") (pintype "passive"))
    )
    (net (code "118") (name "VDD") (class "Default")
      (node (ref "C12") (pin "1") (pinfunction "1_1") (pintype "passive"))
      (node (ref "C14") (pin "1") (pinfunction "1_1") (pintype "passive"))
      (node (ref "C18") (pin "1") (pinfunction "1_1") (pintype "passive"))
      (node (ref "C2") (pin "1") (pinfunction "1_1") (pintype "passive"))
      (node (ref "C22") (pin "1") (pinfunction "1_1") (pintype "passive"))
      (node (ref "C4") (pin "1") (pinfunction "1_1") (pintype "passive"))
      (node (ref "C8") (pin "1") (pinfunction "1_1") (pintype "passive"))
      (node (ref "L2") (pin "1") (pinfunction "1_1") (pintype "passive"))
      (node (ref "U5") (pin "10") (pinfunction "VDDCORE1_10") (pintype "input"))
      (node (ref "U5") (pin "34") (pinfunction "VDDCORE2_34") (pintype "input"))
      (node (ref "U5") (pin "42") (pinfunction "VDDOUT_42") (pintype "output"))
      (node (ref "U5") (pin "45") (pinfunction "VDDCORE3_45") (pintype "input"))
      (node (ref "U5") (pin "71") (pinfunction "VDDCORE4_71") (pintype "input"))
      (node (ref "U5") (pin "89") (pinfunction "VDDCORE5_89") (pintype "input"))
    )
    (net (code "119") (name "unconnected-(J9-PadID)") (class "Default")
      (node (ref "J9") (pin "ID") (pinfunction "ID_ID") (pintype "bidirectional"))
    )
    (net (code "120") (name "unconnected-(JP4-Pad7)") (class "Default")
      (node (ref "JP4") (pin "7") (pinfunction "7_7") (pintype "passive"))
    )
    (net (code "121") (name "unconnected-(S1-Pad2)") (class "Default")
      (node (ref "S1") (pin "2") (pinfunction "2_2") (pintype "passive"))
    )
    (net (code "122") (name "unconnected-(S2-Pad2)") (class "Default")
      (node (ref "S2") (pin "2") (pinfunction "2_2") (pintype "passive"))
    )
    (net (code "123") (name "unconnected-(S2-Pad4)") (class "Default")
      (node (ref "S2") (pin "4") (pinfunction "4_4") (pintype "passive"))
    )
    (net (code "124") (name "unconnected-(U5A-PA0{slash}CANTX0{slash}PWML3-Pad13)") (class "Default")
      (node (ref "U5") (pin "13") (pinfunction "PA0/CANTX0/PWML3_13") (pintype "bidirectional"))
    )
    (net (code "125") (name "unconnected-(U5A-PA16{slash}SPCK1{slash}TD{slash}AD7-Pad56)") (class "Default")
      (node (ref "U5") (pin "56") (pinfunction "PA16/SPCK1/TD/AD7_56") (pintype "bidirectional"))
    )
    (net (code "126") (name "unconnected-(U5B-PB0{slash}TIOA3-Pad80)") (class "Default")
      (node (ref "U5") (pin "80") (pinfunction "PB0/TIOA3_80") (pintype "bidirectional"))
    )
    (net (code "127") (name "unconnected-(U5B-PB1{slash}TIOB3-Pad81)") (class "Default")
      (node (ref "U5") (pin "81") (pinfunction "PB1/TIOB3_81") (pintype "bidirectional"))
    )
    (net (code "128") (name "unconnected-(U5B-PB2{slash}TIOA4-Pad82)") (class "Default")
      (node (ref "U5") (pin "82") (pinfunction "PB2/TIOA4_82") (pintype "bidirectional"))
    )
    (net (code "129") (name "unconnected-(U5B-PB3{slash}TIOB4-Pad83)") (class "Default")
      (node (ref "U5") (pin "83") (pinfunction "PB3/TIOB4_83") (pintype "bidirectional"))
    )
    (net (code "130") (name "unconnected-(U5B-PB4{slash}TIOA5-Pad84)") (class "Default")
      (node (ref "U5") (pin "84") (pinfunction "PB4/TIOA5_84") (pintype "bidirectional"))
    )
    (net (code "131") (name "unconnected-(U5B-PB6{slash}PWML4-Pad86)") (class "Default")
      (node (ref "U5") (pin "86") (pinfunction "PB6/PWML4_86") (pintype "bidirectional"))
    )
    (net (code "132") (name "unconnected-(U5B-PB7{slash}PWML5-Pad87)") (class "Default")
      (node (ref "U5") (pin "87") (pinfunction "PB7/PWML5_87") (pintype "bidirectional"))
    )
    (net (code "133") (name "unconnected-(U5B-PB8{slash}PWML6-Pad88)") (class "Default")
      (node (ref "U5") (pin "88") (pinfunction "PB8/PWML6_88") (pintype "bidirectional"))
    )
    (net (code "134") (name "unconnected-(U5B-PB9{slash}PWML7-Pad92)") (class "Default")
      (node (ref "U5") (pin "92") (pinfunction "PB9/PWML7_92") (pintype "bidirectional"))
    )
    (net (code "135") (name "unconnected-(U5B-PB10{slash}UOTGVBOF{slash}A18-Pad93)") (class "Default")
      (node (ref "U5") (pin "93") (pinfunction "PB10/UOTGVBOF/A18_93") (pintype "bidirectional"))
    )
    (net (code "136") (name "unconnected-(U5B-PB11{slash}UOTGID{slash}A19-Pad94)") (class "Default")
      (node (ref "U5") (pin "94") (pinfunction "PB11/UOTGID/A19_94") (pintype "bidirectional"))
    )
    (net (code "137") (name "unconnected-(U5B-PB27{slash}NCS3{slash}TIOB0-Pad46)") (class "Default")
      (node (ref "U5") (pin "46") (pinfunction "PB27/NCS3/TIOB0_46") (pintype "bidirectional"))
    )
    (net (code "138") (name "unconnected-(U5C-XIN32-Pad36)") (class "Default")
      (node (ref "U5") (pin "36") (pinfunction "XIN32_36") (pintype "output"))
    )
    (net (code "139") (name "unconnected-(U5C-XOUT32-Pad37)") (class "Default")
      (node (ref "U5") (pin "37") (pinfunction "XOUT32_37") (pintype "output"))
    )
  )
)
